# 38_DRAM-LPDDR4X_200P_1X32bit.net
KiCad netlist of a schematic drawn in Altium Designer
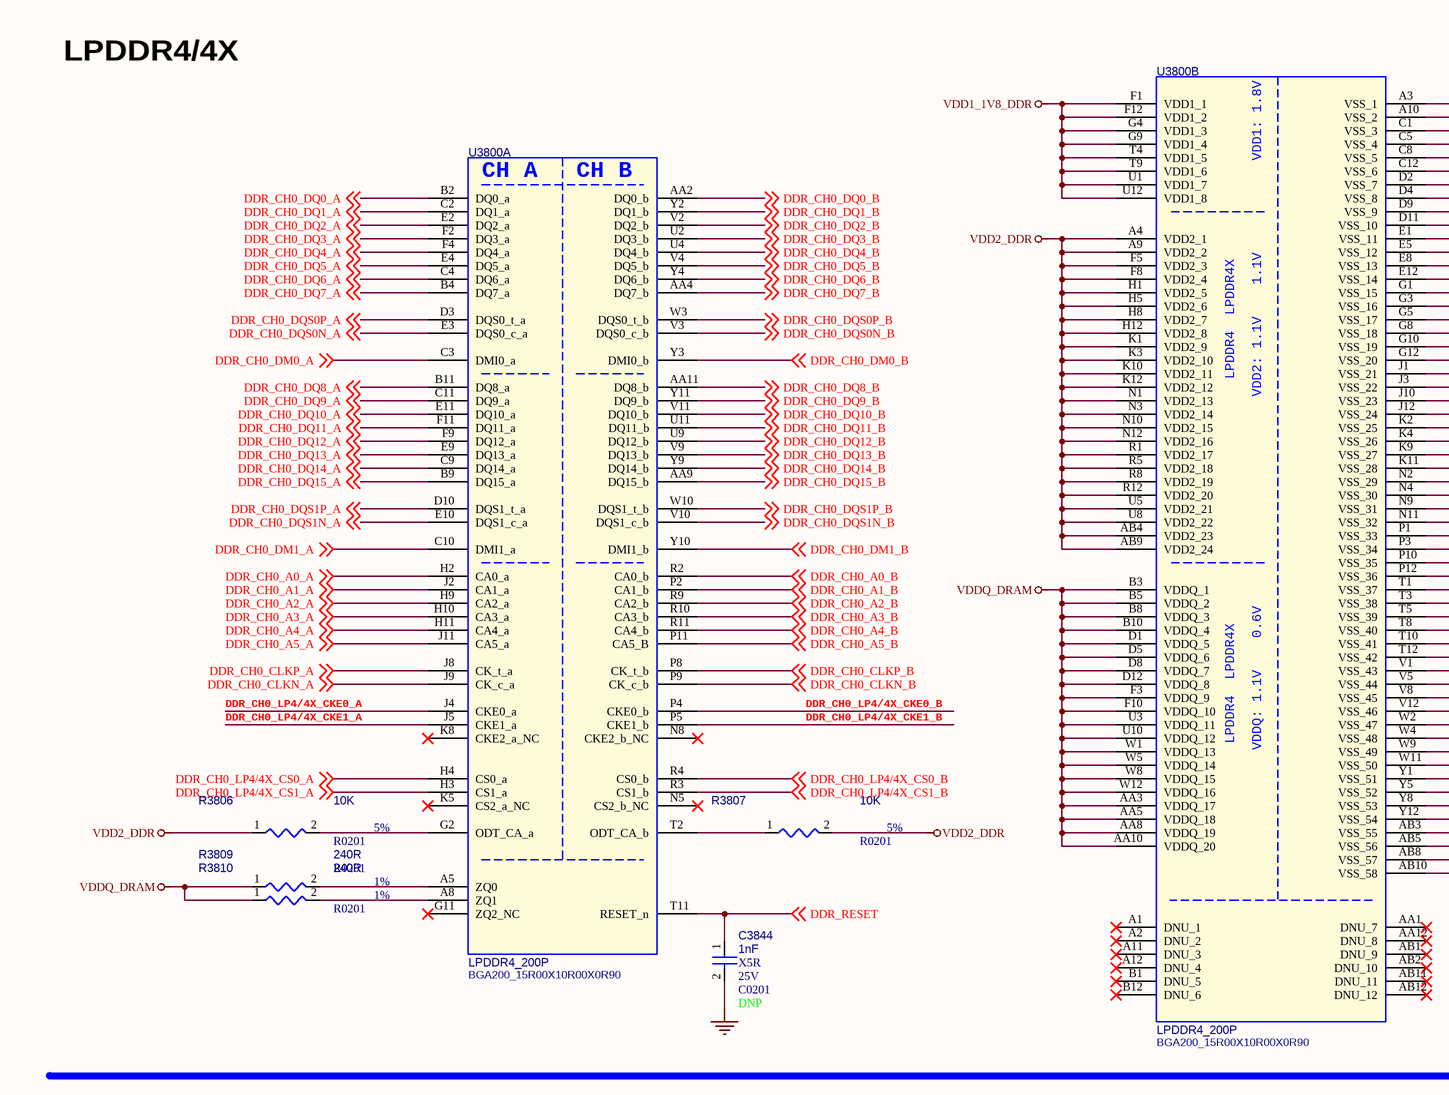
[diagram p0: 38.DRAM-LPDDR4X_200P_1X32bit.SchDoc, top left]
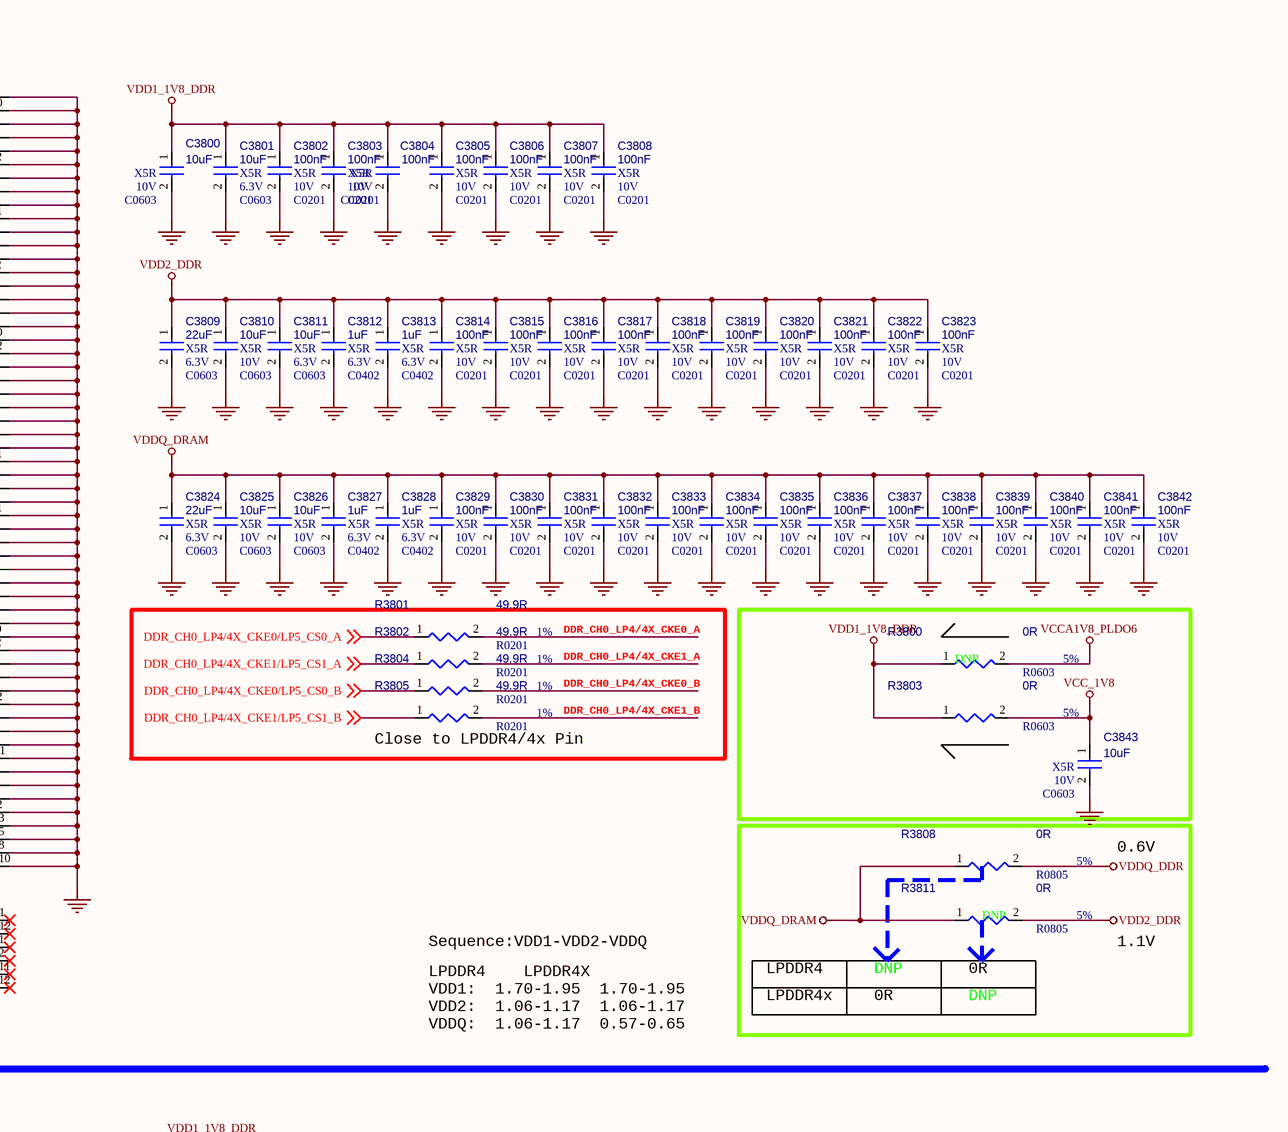
[diagram p1: 38.DRAM-LPDDR4X_200P_1X32bit.SchDoc, top right]
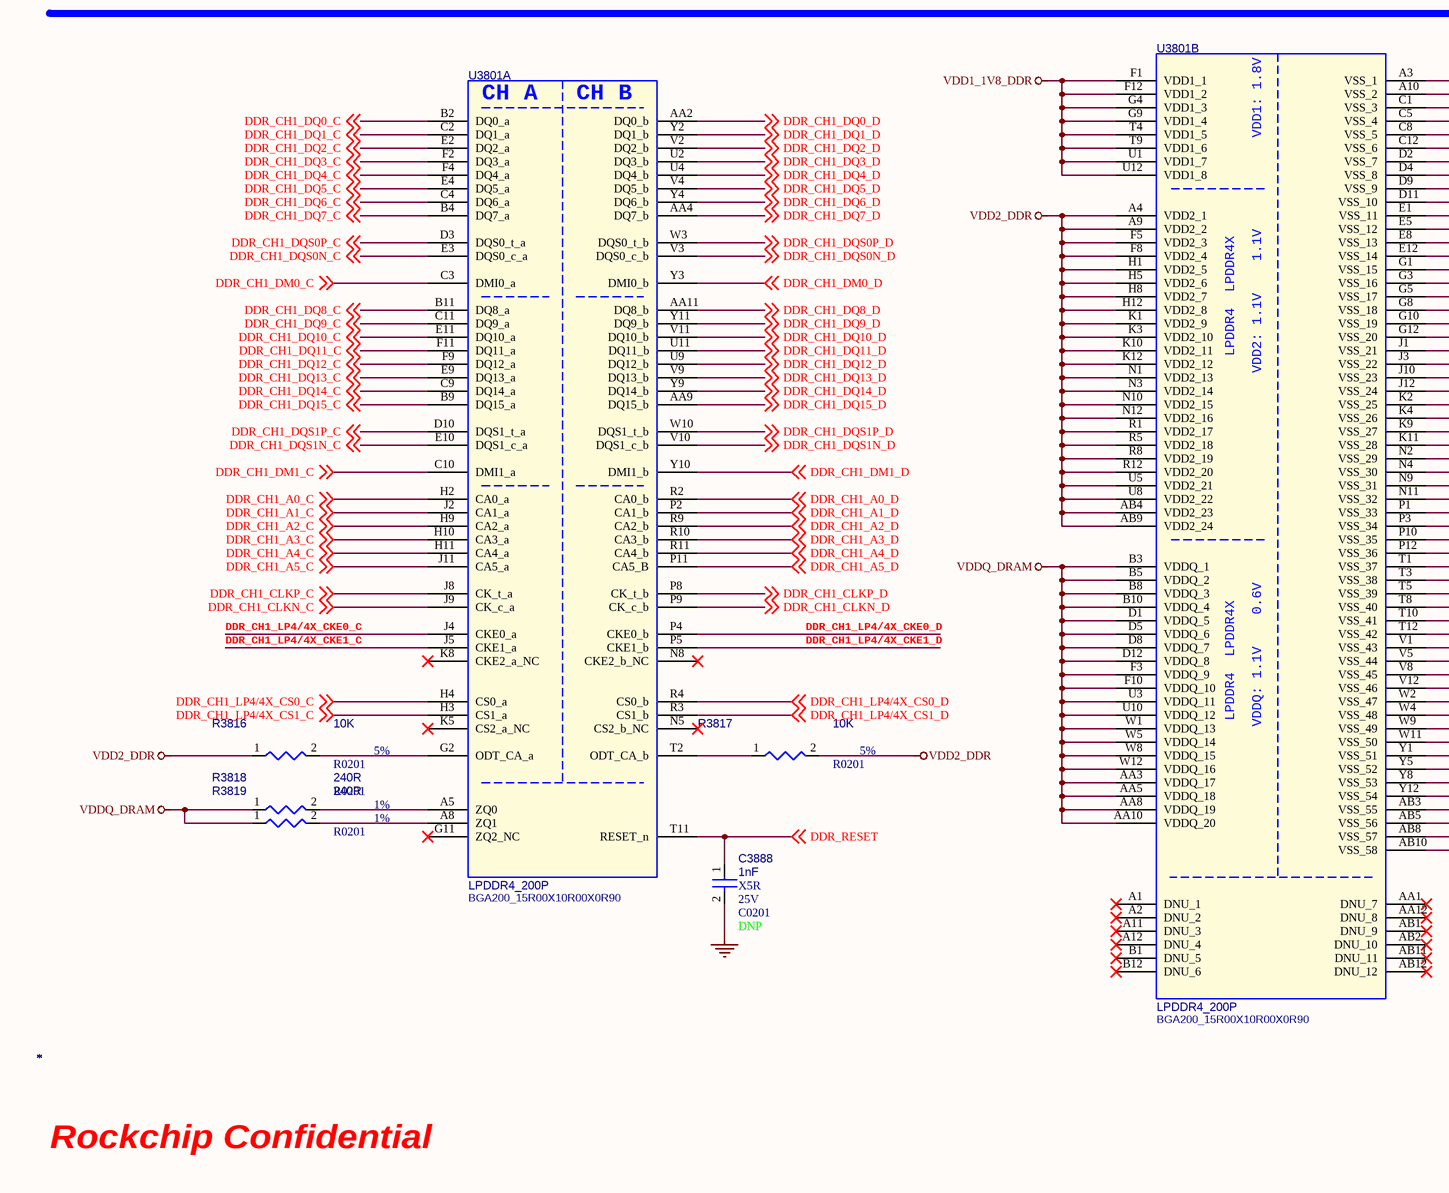
[diagram p2: 38.DRAM-LPDDR4X_200P_1X32bit.SchDoc, bottom left]
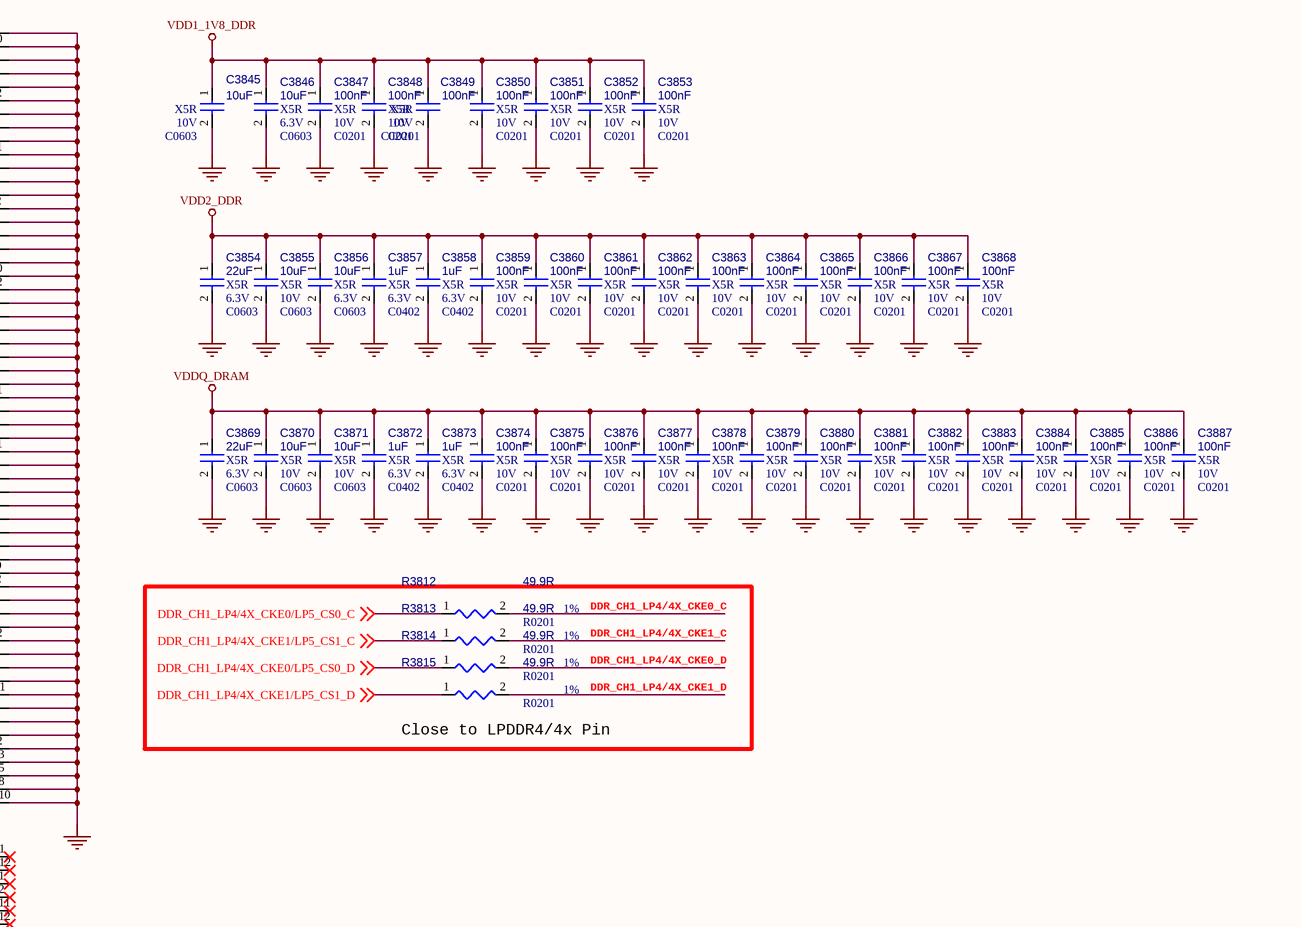
[diagram p3: 38.DRAM-LPDDR4X_200P_1X32bit.SchDoc, bottom right]

(export (version "E")
  (design (tool "Eeschema 10.0.6"))
  (components
    (comp (ref "C3800")
      (value "*")
      (footprint "C0603")
      (description "cap,10.00uF,+/-10%,10V,X5R,C0603")
      (fields
        (field (name "VOLTAGE") "10V")
        (field (name "PCB FOOTPRINT") "C0603")
        (field (name "DIELECTRIC") "X5R")
        (field (name "TOLERANCE") "10%")
        (field (name "MANUFACTURER") "TDK")
        (field (name "ALTIUM_UNNAMED_1") "10uF")
        (field (name "CREATED BY") "JJJ")
      )
      (libsource (lib "*") (part "CAP NP"))
    )
    (comp (ref "C3801")
      (value "*")
      (footprint "C0603")
      (description "cap,10.00uF,+/-10%,6.3V,X5R,C0603")
      (fields
        (field (name "VOLTAGE") "6.3V")
        (field (name "PCB FOOTPRINT") "C0603")
        (field (name "DIELECTRIC") "X5R")
        (field (name "TOLERANCE") "10%")
        (field (name "MANUFACTURER") "TDK")
        (field (name "ALTIUM_UNNAMED_1") "10uF")
        (field (name "CREATED BY") "JJJ")
      )
      (libsource (lib "*") (part "CAP NP"))
    )
    (comp (ref "C3802")
      (value "*")
      (footprint "C0201")
      (description "cap,100.00nF,+/-10%,10V,X5R,C0201")
      (fields
        (field (name "VOLTAGE") "10V")
        (field (name "PCB FOOTPRINT") "C0201")
        (field (name "DIELECTRIC") "X5R")
        (field (name "MANUFACTURER") "TDK")
        (field (name "TOLERANCE") "10%")
        (field (name "ALTIUM_UNNAMED_1") "100nF")
        (field (name "CREATED BY") "JJJ")
      )
      (libsource (lib "*") (part "CAP NP"))
    )
    (comp (ref "C3803")
      (value "*")
      (footprint "C0201")
      (description "cap,100.00nF,+/-10%,10V,X5R,C0201")
      (fields
        (field (name "VOLTAGE") "10V")
        (field (name "PCB FOOTPRINT") "C0201")
        (field (name "DIELECTRIC") "X5R")
        (field (name "TOLERANCE") "10%")
        (field (name "MANUFACTURER") "TDK")
        (field (name "ALTIUM_UNNAMED_1") "100nF")
        (field (name "CREATED BY") "JJJ")
      )
      (libsource (lib "*") (part "CAP NP"))
    )
    (comp (ref "C3804")
      (value "*")
      (footprint "C0201")
      (description "cap,100.00nF,+/-10%,10V,X5R,C0201")
      (fields
        (field (name "VOLTAGE") "10V")
        (field (name "PCB FOOTPRINT") "C0201")
        (field (name "DIELECTRIC") "X5R")
        (field (name "MANUFACTURER") "TDK")
        (field (name "TOLERANCE") "10%")
        (field (name "ALTIUM_UNNAMED_1") "100nF")
        (field (name "CREATED BY") "JJJ")
      )
      (libsource (lib "*") (part "CAP NP"))
    )
    (comp (ref "C3805")
      (value "*")
      (footprint "C0201")
      (description "cap,100.00nF,+/-10%,10V,X5R,C0201")
      (fields
        (field (name "VOLTAGE") "10V")
        (field (name "PCB FOOTPRINT") "C0201")
        (field (name "DIELECTRIC") "X5R")
        (field (name "MANUFACTURER") "TDK")
        (field (name "TOLERANCE") "10%")
        (field (name "ALTIUM_UNNAMED_1") "100nF")
        (field (name "CREATED BY") "JJJ")
      )
      (libsource (lib "*") (part "CAP NP"))
    )
    (comp (ref "C3806")
      (value "*")
      (footprint "C0201")
      (description "cap,100.00nF,+/-10%,10V,X5R,C0201")
      (fields
        (field (name "VOLTAGE") "10V")
        (field (name "PCB FOOTPRINT") "C0201")
        (field (name "DIELECTRIC") "X5R")
        (field (name "MANUFACTURER") "TDK")
        (field (name "TOLERANCE") "10%")
        (field (name "ALTIUM_UNNAMED_1") "100nF")
        (field (name "CREATED BY") "JJJ")
      )
      (libsource (lib "*") (part "CAP NP"))
    )
    (comp (ref "C3807")
      (value "*")
      (footprint "C0201")
      (description "cap,100.00nF,+/-10%,10V,X5R,C0201")
      (fields
        (field (name "VOLTAGE") "10V")
        (field (name "PCB FOOTPRINT") "C0201")
        (field (name "DIELECTRIC") "X5R")
        (field (name "TOLERANCE") "10%")
        (field (name "MANUFACTURER") "TDK")
        (field (name "ALTIUM_UNNAMED_1") "100nF")
        (field (name "CREATED BY") "JJJ")
      )
      (libsource (lib "*") (part "CAP NP"))
    )
    (comp (ref "C3808")
      (value "*")
      (footprint "C0201")
      (description "cap,100.00nF,+/-10%,10V,X5R,C0201")
      (fields
        (field (name "VOLTAGE") "10V")
        (field (name "PCB FOOTPRINT") "C0201")
        (field (name "DIELECTRIC") "X5R")
        (field (name "TOLERANCE") "10%")
        (field (name "MANUFACTURER") "TDK")
        (field (name "ALTIUM_UNNAMED_1") "100nF")
        (field (name "CREATED BY") "JJJ")
      )
      (libsource (lib "*") (part "CAP NP"))
    )
    (comp (ref "C3809")
      (value "*")
      (footprint "C0603")
      (description "cap,22.00uF,+/-20%,6.3V,X5R,C0603")
      (fields
        (field (name "VOLTAGE") "6.3V")
        (field (name "PCB FOOTPRINT") "C0603")
        (field (name "DIELECTRIC") "X5R")
        (field (name "TOLERANCE") "20%")
        (field (name "MANUFACTURER") "TDK")
        (field (name "ALTIUM_UNNAMED_1") "22uF")
        (field (name "CREATED BY") "JJJ")
      )
      (libsource (lib "*") (part "CAP NP"))
    )
    (comp (ref "C3810")
      (value "*")
      (footprint "C0603")
      (description "cap,10.00uF,+/-10%,10V,X5R,C0603")
      (fields
        (field (name "VOLTAGE") "10V")
        (field (name "PCB FOOTPRINT") "C0603")
        (field (name "DIELECTRIC") "X5R")
        (field (name "TOLERANCE") "10%")
        (field (name "MANUFACTURER") "TDK")
        (field (name "ALTIUM_UNNAMED_1") "10uF")
        (field (name "CREATED BY") "JJJ")
      )
      (libsource (lib "*") (part "CAP NP"))
    )
    (comp (ref "C3811")
      (value "*")
      (footprint "C0603")
      (description "cap,10.00uF,+/-10%,6.3V,X5R,C0603")
      (fields
        (field (name "VOLTAGE") "6.3V")
        (field (name "PCB FOOTPRINT") "C0603")
        (field (name "DIELECTRIC") "X5R")
        (field (name "TOLERANCE") "10%")
        (field (name "MANUFACTURER") "TDK")
        (field (name "ALTIUM_UNNAMED_1") "10uF")
        (field (name "CREATED BY") "JJJ")
      )
      (libsource (lib "*") (part "CAP NP"))
    )
    (comp (ref "C3812")
      (value "*")
      (footprint "C0402")
      (description "cap,1.00uF,+/-10%,6.3V,X5R,C0402")
      (fields
        (field (name "VOLTAGE") "6.3V")
        (field (name "PCB FOOTPRINT") "C0402")
        (field (name "DIELECTRIC") "X5R")
        (field (name "TOLERANCE") "10%")
        (field (name "MANUFACTURER") "TDK")
        (field (name "ALTIUM_UNNAMED_1") "1uF")
        (field (name "CREATED BY") "JJJ")
      )
      (libsource (lib "*") (part "CAP NP"))
    )
    (comp (ref "C3813")
      (value "*")
      (footprint "C0402")
      (description "cap,1.00uF,+/-10%,6.3V,X5R,C0402")
      (fields
        (field (name "VOLTAGE") "6.3V")
        (field (name "PCB FOOTPRINT") "C0402")
        (field (name "DIELECTRIC") "X5R")
        (field (name "TOLERANCE") "10%")
        (field (name "MANUFACTURER") "TDK")
        (field (name "ALTIUM_UNNAMED_1") "1uF")
        (field (name "CREATED BY") "JJJ")
      )
      (libsource (lib "*") (part "CAP NP"))
    )
    (comp (ref "C3814")
      (value "*")
      (footprint "C0201")
      (description "cap,100.00nF,+/-10%,10V,X5R,C0201")
      (fields
        (field (name "VOLTAGE") "10V")
        (field (name "PCB FOOTPRINT") "C0201")
        (field (name "DIELECTRIC") "X5R")
        (field (name "TOLERANCE") "10%")
        (field (name "MANUFACTURER") "TDK")
        (field (name "ALTIUM_UNNAMED_1") "100nF")
        (field (name "CREATED BY") "JJJ")
      )
      (libsource (lib "*") (part "CAP NP"))
    )
    (comp (ref "C3815")
      (value "*")
      (footprint "C0201")
      (description "cap,100.00nF,+/-10%,10V,X5R,C0201")
      (fields
        (field (name "VOLTAGE") "10V")
        (field (name "PCB FOOTPRINT") "C0201")
        (field (name "DIELECTRIC") "X5R")
        (field (name "TOLERANCE") "10%")
        (field (name "MANUFACTURER") "TDK")
        (field (name "ALTIUM_UNNAMED_1") "100nF")
        (field (name "CREATED BY") "JJJ")
      )
      (libsource (lib "*") (part "CAP NP"))
    )
    (comp (ref "C3816")
      (value "*")
      (footprint "C0201")
      (description "cap,100.00nF,+/-10%,10V,X5R,C0201")
      (fields
        (field (name "VOLTAGE") "10V")
        (field (name "PCB FOOTPRINT") "C0201")
        (field (name "DIELECTRIC") "X5R")
        (field (name "MANUFACTURER") "TDK")
        (field (name "TOLERANCE") "10%")
        (field (name "ALTIUM_UNNAMED_1") "100nF")
        (field (name "CREATED BY") "JJJ")
      )
      (libsource (lib "*") (part "CAP NP"))
    )
    (comp (ref "C3817")
      (value "*")
      (footprint "C0201")
      (description "cap,100.00nF,+/-10%,10V,X5R,C0201")
      (fields
        (field (name "VOLTAGE") "10V")
        (field (name "PCB FOOTPRINT") "C0201")
        (field (name "DIELECTRIC") "X5R")
        (field (name "TOLERANCE") "10%")
        (field (name "MANUFACTURER") "TDK")
        (field (name "ALTIUM_UNNAMED_1") "100nF")
        (field (name "CREATED BY") "JJJ")
      )
      (libsource (lib "*") (part "CAP NP"))
    )
    (comp (ref "C3818")
      (value "*")
      (footprint "C0201")
      (description "cap,100.00nF,+/-10%,10V,X5R,C0201")
      (fields
        (field (name "VOLTAGE") "10V")
        (field (name "PCB FOOTPRINT") "C0201")
        (field (name "DIELECTRIC") "X5R")
        (field (name "TOLERANCE") "10%")
        (field (name "MANUFACTURER") "TDK")
        (field (name "ALTIUM_UNNAMED_1") "100nF")
        (field (name "CREATED BY") "JJJ")
      )
      (libsource (lib "*") (part "CAP NP"))
    )
    (comp (ref "C3819")
      (value "*")
      (footprint "C0201")
      (description "cap,100.00nF,+/-10%,10V,X5R,C0201")
      (fields
        (field (name "VOLTAGE") "10V")
        (field (name "PCB FOOTPRINT") "C0201")
        (field (name "DIELECTRIC") "X5R")
        (field (name "MANUFACTURER") "TDK")
        (field (name "TOLERANCE") "10%")
        (field (name "ALTIUM_UNNAMED_1") "100nF")
        (field (name "CREATED BY") "JJJ")
      )
      (libsource (lib "*") (part "CAP NP"))
    )
    (comp (ref "C3820")
      (value "*")
      (footprint "C0201")
      (description "cap,100.00nF,+/-10%,10V,X5R,C0201")
      (fields
        (field (name "VOLTAGE") "10V")
        (field (name "PCB FOOTPRINT") "C0201")
        (field (name "DIELECTRIC") "X5R")
        (field (name "MANUFACTURER") "TDK")
        (field (name "TOLERANCE") "10%")
        (field (name "ALTIUM_UNNAMED_1") "100nF")
        (field (name "CREATED BY") "JJJ")
      )
      (libsource (lib "*") (part "CAP NP"))
    )
    (comp (ref "C3821")
      (value "*")
      (footprint "C0201")
      (description "cap,100.00nF,+/-10%,10V,X5R,C0201")
      (fields
        (field (name "VOLTAGE") "10V")
        (field (name "PCB FOOTPRINT") "C0201")
        (field (name "DIELECTRIC") "X5R")
        (field (name "TOLERANCE") "10%")
        (field (name "MANUFACTURER") "TDK")
        (field (name "ALTIUM_UNNAMED_1") "100nF")
        (field (name "CREATED BY") "JJJ")
      )
      (libsource (lib "*") (part "CAP NP"))
    )
    (comp (ref "C3822")
      (value "*")
      (footprint "C0201")
      (description "cap,100.00nF,+/-10%,10V,X5R,C0201")
      (fields
        (field (name "VOLTAGE") "10V")
        (field (name "PCB FOOTPRINT") "C0201")
        (field (name "DIELECTRIC") "X5R")
        (field (name "MANUFACTURER") "TDK")
        (field (name "TOLERANCE") "10%")
        (field (name "ALTIUM_UNNAMED_1") "100nF")
        (field (name "CREATED BY") "JJJ")
      )
      (libsource (lib "*") (part "CAP NP"))
    )
    (comp (ref "C3823")
      (value "*")
      (footprint "C0201")
      (description "cap,100.00nF,+/-10%,10V,X5R,C0201")
      (fields
        (field (name "VOLTAGE") "10V")
        (field (name "PCB FOOTPRINT") "C0201")
        (field (name "DIELECTRIC") "X5R")
        (field (name "TOLERANCE") "10%")
        (field (name "MANUFACTURER") "TDK")
        (field (name "ALTIUM_UNNAMED_1") "100nF")
        (field (name "CREATED BY") "JJJ")
      )
      (libsource (lib "*") (part "CAP NP"))
    )
    (comp (ref "C3824")
      (value "*")
      (footprint "C0603")
      (description "cap,22.00uF,+/-20%,6.3V,X5R,C0603")
      (fields
        (field (name "VOLTAGE") "6.3V")
        (field (name "PCB FOOTPRINT") "C0603")
        (field (name "DIELECTRIC") "X5R")
        (field (name "MANUFACTURER") "TDK")
        (field (name "TOLERANCE") "20%")
        (field (name "ALTIUM_UNNAMED_1") "22uF")
        (field (name "CREATED BY") "JJJ")
      )
      (libsource (lib "*") (part "CAP NP"))
    )
    (comp (ref "C3825")
      (value "*")
      (footprint "C0603")
      (description "cap,10.00uF,+/-10%,10V,X5R,C0603")
      (fields
        (field (name "VOLTAGE") "10V")
        (field (name "PCB FOOTPRINT") "C0603")
        (field (name "DIELECTRIC") "X5R")
        (field (name "TOLERANCE") "10%")
        (field (name "MANUFACTURER") "TDK")
        (field (name "ALTIUM_UNNAMED_1") "10uF")
        (field (name "CREATED BY") "JJJ")
      )
      (libsource (lib "*") (part "CAP NP"))
    )
    (comp (ref "C3826")
      (value "*")
      (footprint "C0603")
      (description "cap,10.00uF,+/-10%,10V,X5R,C0603")
      (fields
        (field (name "VOLTAGE") "10V")
        (field (name "PCB FOOTPRINT") "C0603")
        (field (name "DIELECTRIC") "X5R")
        (field (name "MANUFACTURER") "TDK")
        (field (name "TOLERANCE") "10%")
        (field (name "ALTIUM_UNNAMED_1") "10uF")
        (field (name "CREATED BY") "JJJ")
      )
      (libsource (lib "*") (part "CAP NP"))
    )
    (comp (ref "C3827")
      (value "*")
      (footprint "C0402")
      (description "cap,1.00uF,+/-10%,6.3V,X5R,C0402")
      (fields
        (field (name "VOLTAGE") "6.3V")
        (field (name "PCB FOOTPRINT") "C0402")
        (field (name "DIELECTRIC") "X5R")
        (field (name "MANUFACTURER") "TDK")
        (field (name "TOLERANCE") "10%")
        (field (name "ALTIUM_UNNAMED_1") "1uF")
        (field (name "CREATED BY") "JJJ")
      )
      (libsource (lib "*") (part "CAP NP"))
    )
    (comp (ref "C3828")
      (value "*")
      (footprint "C0402")
      (description "cap,1.00uF,+/-10%,6.3V,X5R,C0402")
      (fields
        (field (name "VOLTAGE") "6.3V")
        (field (name "PCB FOOTPRINT") "C0402")
        (field (name "DIELECTRIC") "X5R")
        (field (name "MANUFACTURER") "TDK")
        (field (name "TOLERANCE") "10%")
        (field (name "ALTIUM_UNNAMED_1") "1uF")
        (field (name "CREATED BY") "JJJ")
      )
      (libsource (lib "*") (part "CAP NP"))
    )
    (comp (ref "C3829")
      (value "*")
      (footprint "C0201")
      (description "cap,100.00nF,+/-10%,10V,X5R,C0201")
      (fields
        (field (name "VOLTAGE") "10V")
        (field (name "PCB FOOTPRINT") "C0201")
        (field (name "DIELECTRIC") "X5R")
        (field (name "MANUFACTURER") "TDK")
        (field (name "TOLERANCE") "10%")
        (field (name "ALTIUM_UNNAMED_1") "100nF")
        (field (name "CREATED BY") "JJJ")
      )
      (libsource (lib "*") (part "CAP NP"))
    )
    (comp (ref "C3830")
      (value "*")
      (footprint "C0201")
      (description "cap,100.00nF,+/-10%,10V,X5R,C0201")
      (fields
        (field (name "VOLTAGE") "10V")
        (field (name "PCB FOOTPRINT") "C0201")
        (field (name "DIELECTRIC") "X5R")
        (field (name "MANUFACTURER") "TDK")
        (field (name "TOLERANCE") "10%")
        (field (name "ALTIUM_UNNAMED_1") "100nF")
        (field (name "CREATED BY") "JJJ")
      )
      (libsource (lib "*") (part "CAP NP"))
    )
    (comp (ref "C3831")
      (value "*")
      (footprint "C0201")
      (description "cap,100.00nF,+/-10%,10V,X5R,C0201")
      (fields
        (field (name "VOLTAGE") "10V")
        (field (name "PCB FOOTPRINT") "C0201")
        (field (name "DIELECTRIC") "X5R")
        (field (name "MANUFACTURER") "TDK")
        (field (name "TOLERANCE") "10%")
        (field (name "ALTIUM_UNNAMED_1") "100nF")
        (field (name "CREATED BY") "JJJ")
      )
      (libsource (lib "*") (part "CAP NP"))
    )
    (comp (ref "C3832")
      (value "*")
      (footprint "C0201")
      (description "cap,100.00nF,+/-10%,10V,X5R,C0201")
      (fields
        (field (name "VOLTAGE") "10V")
        (field (name "PCB FOOTPRINT") "C0201")
        (field (name "DIELECTRIC") "X5R")
        (field (name "TOLERANCE") "10%")
        (field (name "MANUFACTURER") "TDK")
        (field (name "ALTIUM_UNNAMED_1") "100nF")
        (field (name "CREATED BY") "JJJ")
      )
      (libsource (lib "*") (part "CAP NP"))
    )
    (comp (ref "C3833")
      (value "*")
      (footprint "C0201")
      (description "cap,100.00nF,+/-10%,10V,X5R,C0201")
      (fields
        (field (name "VOLTAGE") "10V")
        (field (name "PCB FOOTPRINT") "C0201")
        (field (name "DIELECTRIC") "X5R")
        (field (name "TOLERANCE") "10%")
        (field (name "MANUFACTURER") "TDK")
        (field (name "ALTIUM_UNNAMED_1") "100nF")
        (field (name "CREATED BY") "JJJ")
      )
      (libsource (lib "*") (part "CAP NP"))
    )
    (comp (ref "C3834")
      (value "*")
      (footprint "C0201")
      (description "cap,100.00nF,+/-10%,10V,X5R,C0201")
      (fields
        (field (name "VOLTAGE") "10V")
        (field (name "PCB FOOTPRINT") "C0201")
        (field (name "DIELECTRIC") "X5R")
        (field (name "TOLERANCE") "10%")
        (field (name "MANUFACTURER") "TDK")
        (field (name "ALTIUM_UNNAMED_1") "100nF")
        (field (name "CREATED BY") "JJJ")
      )
      (libsource (lib "*") (part "CAP NP"))
    )
    (comp (ref "C3835")
      (value "*")
      (footprint "C0201")
      (description "cap,100.00nF,+/-10%,10V,X5R,C0201")
      (fields
        (field (name "VOLTAGE") "10V")
        (field (name "PCB FOOTPRINT") "C0201")
        (field (name "DIELECTRIC") "X5R")
        (field (name "MANUFACTURER") "TDK")
        (field (name "TOLERANCE") "10%")
        (field (name "ALTIUM_UNNAMED_1") "100nF")
        (field (name "CREATED BY") "JJJ")
      )
      (libsource (lib "*") (part "CAP NP"))
    )
    (comp (ref "C3836")
      (value "*")
      (footprint "C0201")
      (description "cap,100.00nF,+/-10%,10V,X5R,C0201")
      (fields
        (field (name "VOLTAGE") "10V")
        (field (name "PCB FOOTPRINT") "C0201")
        (field (name "DIELECTRIC") "X5R")
        (field (name "TOLERANCE") "10%")
        (field (name "MANUFACTURER") "TDK")
        (field (name "ALTIUM_UNNAMED_1") "100nF")
        (field (name "CREATED BY") "JJJ")
      )
      (libsource (lib "*") (part "CAP NP"))
    )
    (comp (ref "C3837")
      (value "*")
      (footprint "C0201")
      (description "cap,100.00nF,+/-10%,10V,X5R,C0201")
      (fields
        (field (name "VOLTAGE") "10V")
        (field (name "PCB FOOTPRINT") "C0201")
        (field (name "DIELECTRIC") "X5R")
        (field (name "TOLERANCE") "10%")
        (field (name "MANUFACTURER") "TDK")
        (field (name "ALTIUM_UNNAMED_1") "100nF")
        (field (name "CREATED BY") "JJJ")
      )
      (libsource (lib "*") (part "CAP NP"))
    )
    (comp (ref "C3838")
      (value "*")
      (footprint "C0201")
      (description "cap,100.00nF,+/-10%,10V,X5R,C0201")
      (fields
        (field (name "VOLTAGE") "10V")
        (field (name "PCB FOOTPRINT") "C0201")
        (field (name "DIELECTRIC") "X5R")
        (field (name "MANUFACTURER") "TDK")
        (field (name "TOLERANCE") "10%")
        (field (name "ALTIUM_UNNAMED_1") "100nF")
        (field (name "CREATED BY") "JJJ")
      )
      (libsource (lib "*") (part "CAP NP"))
    )
    (comp (ref "C3839")
      (value "*")
      (footprint "C0201")
      (description "cap,100.00nF,+/-10%,10V,X5R,C0201")
      (fields
        (field (name "VOLTAGE") "10V")
        (field (name "PCB FOOTPRINT") "C0201")
        (field (name "DIELECTRIC") "X5R")
        (field (name "TOLERANCE") "10%")
        (field (name "MANUFACTURER") "TDK")
        (field (name "ALTIUM_UNNAMED_1") "100nF")
        (field (name "CREATED BY") "JJJ")
      )
      (libsource (lib "*") (part "CAP NP"))
    )
    (comp (ref "C3840")
      (value "*")
      (footprint "C0201")
      (description "cap,100.00nF,+/-10%,10V,X5R,C0201")
      (fields
        (field (name "VOLTAGE") "10V")
        (field (name "PCB FOOTPRINT") "C0201")
        (field (name "DIELECTRIC") "X5R")
        (field (name "MANUFACTURER") "TDK")
        (field (name "TOLERANCE") "10%")
        (field (name "ALTIUM_UNNAMED_1") "100nF")
        (field (name "CREATED BY") "JJJ")
      )
      (libsource (lib "*") (part "CAP NP"))
    )
    (comp (ref "C3841")
      (value "*")
      (footprint "C0201")
      (description "cap,100.00nF,+/-10%,10V,X5R,C0201")
      (fields
        (field (name "VOLTAGE") "10V")
        (field (name "PCB FOOTPRINT") "C0201")
        (field (name "DIELECTRIC") "X5R")
        (field (name "MANUFACTURER") "TDK")
        (field (name "TOLERANCE") "10%")
        (field (name "ALTIUM_UNNAMED_1") "100nF")
        (field (name "CREATED BY") "JJJ")
      )
      (libsource (lib "*") (part "CAP NP"))
    )
    (comp (ref "C3842")
      (value "*")
      (footprint "C0201")
      (description "cap,100.00nF,+/-10%,10V,X5R,C0201")
      (fields
        (field (name "VOLTAGE") "10V")
        (field (name "PCB FOOTPRINT") "C0201")
        (field (name "DIELECTRIC") "X5R")
        (field (name "MANUFACTURER") "TDK")
        (field (name "TOLERANCE") "10%")
        (field (name "ALTIUM_UNNAMED_1") "100nF")
        (field (name "CREATED BY") "JJJ")
      )
      (libsource (lib "*") (part "CAP NP"))
    )
    (comp (ref "C3843")
      (value "*")
      (footprint "C0603")
      (description "cap,10.00uF,+/-10%,10V,X5R,C0603")
      (fields
        (field (name "VOLTAGE") "10V")
        (field (name "PCB FOOTPRINT") "C0603")
        (field (name "DIELECTRIC") "X5R")
        (field (name "MANUFACTURER") "TDK")
        (field (name "TOLERANCE") "10%")
        (field (name "ALTIUM_UNNAMED_1") "10uF")
        (field (name "CREATED BY") "JJJ")
      )
      (libsource (lib "*") (part "CAP NP"))
    )
    (comp (ref "C3844")
      (value "*")
      (footprint "C0201")
      (description "cap,1.00nF,+/-10%,25V,X5R,C0201")
      (fields
        (field (name "VOLTAGE") "25V")
        (field (name "PCB FOOTPRINT") "C0201")
        (field (name "DIELECTRIC") "X5R")
        (field (name "MANUFACTURER") "TDK")
        (field (name "TOLERANCE") "10%")
        (field (name "OPTION") "DNP")
        (field (name "ALTIUM_UNNAMED_1") "1nF")
        (field (name "CREATED BY") "JJJ")
      )
      (libsource (lib "*") (part "CAP NP"))
    )
    (comp (ref "C3845")
      (value "*")
      (footprint "C0603")
      (description "cap,10.00uF,+/-10%,10V,X5R,C0603")
      (fields
        (field (name "VOLTAGE") "10V")
        (field (name "PCB FOOTPRINT") "C0603")
        (field (name "DIELECTRIC") "X5R")
        (field (name "TOLERANCE") "10%")
        (field (name "MANUFACTURER") "TDK")
        (field (name "ALTIUM_UNNAMED_1") "10uF")
        (field (name "CREATED BY") "JJJ")
      )
      (libsource (lib "*") (part "CAP NP"))
    )
    (comp (ref "C3846")
      (value "*")
      (footprint "C0603")
      (description "cap,10.00uF,+/-10%,6.3V,X5R,C0603")
      (fields
        (field (name "VOLTAGE") "6.3V")
        (field (name "PCB FOOTPRINT") "C0603")
        (field (name "DIELECTRIC") "X5R")
        (field (name "TOLERANCE") "10%")
        (field (name "MANUFACTURER") "TDK")
        (field (name "ALTIUM_UNNAMED_1") "10uF")
        (field (name "CREATED BY") "JJJ")
      )
      (libsource (lib "*") (part "CAP NP"))
    )
    (comp (ref "C3847")
      (value "*")
      (footprint "C0201")
      (description "cap,100.00nF,+/-10%,10V,X5R,C0201")
      (fields
        (field (name "VOLTAGE") "10V")
        (field (name "PCB FOOTPRINT") "C0201")
        (field (name "DIELECTRIC") "X5R")
        (field (name "MANUFACTURER") "TDK")
        (field (name "TOLERANCE") "10%")
        (field (name "ALTIUM_UNNAMED_1") "100nF")
        (field (name "CREATED BY") "JJJ")
      )
      (libsource (lib "*") (part "CAP NP"))
    )
    (comp (ref "C3848")
      (value "*")
      (footprint "C0201")
      (description "cap,100.00nF,+/-10%,10V,X5R,C0201")
      (fields
        (field (name "VOLTAGE") "10V")
        (field (name "PCB FOOTPRINT") "C0201")
        (field (name "DIELECTRIC") "X5R")
        (field (name "TOLERANCE") "10%")
        (field (name "MANUFACTURER") "TDK")
        (field (name "ALTIUM_UNNAMED_1") "100nF")
        (field (name "CREATED BY") "JJJ")
      )
      (libsource (lib "*") (part "CAP NP"))
    )
    (comp (ref "C3849")
      (value "*")
      (footprint "C0201")
      (description "cap,100.00nF,+/-10%,10V,X5R,C0201")
      (fields
        (field (name "VOLTAGE") "10V")
        (field (name "PCB FOOTPRINT") "C0201")
        (field (name "DIELECTRIC") "X5R")
        (field (name "MANUFACTURER") "TDK")
        (field (name "TOLERANCE") "10%")
        (field (name "ALTIUM_UNNAMED_1") "100nF")
        (field (name "CREATED BY") "JJJ")
      )
      (libsource (lib "*") (part "CAP NP"))
    )
    (comp (ref "C3850")
      (value "*")
      (footprint "C0201")
      (description "cap,100.00nF,+/-10%,10V,X5R,C0201")
      (fields
        (field (name "VOLTAGE") "10V")
        (field (name "PCB FOOTPRINT") "C0201")
        (field (name "DIELECTRIC") "X5R")
        (field (name "MANUFACTURER") "TDK")
        (field (name "TOLERANCE") "10%")
        (field (name "ALTIUM_UNNAMED_1") "100nF")
        (field (name "CREATED BY") "JJJ")
      )
      (libsource (lib "*") (part "CAP NP"))
    )
    (comp (ref "C3851")
      (value "*")
      (footprint "C0201")
      (description "cap,100.00nF,+/-10%,10V,X5R,C0201")
      (fields
        (field (name "VOLTAGE") "10V")
        (field (name "PCB FOOTPRINT") "C0201")
        (field (name "DIELECTRIC") "X5R")
        (field (name "MANUFACTURER") "TDK")
        (field (name "TOLERANCE") "10%")
        (field (name "ALTIUM_UNNAMED_1") "100nF")
        (field (name "CREATED BY") "JJJ")
      )
      (libsource (lib "*") (part "CAP NP"))
    )
    (comp (ref "C3852")
      (value "*")
      (footprint "C0201")
      (description "cap,100.00nF,+/-10%,10V,X5R,C0201")
      (fields
        (field (name "VOLTAGE") "10V")
        (field (name "PCB FOOTPRINT") "C0201")
        (field (name "DIELECTRIC") "X5R")
        (field (name "TOLERANCE") "10%")
        (field (name "MANUFACTURER") "TDK")
        (field (name "ALTIUM_UNNAMED_1") "100nF")
        (field (name "CREATED BY") "JJJ")
      )
      (libsource (lib "*") (part "CAP NP"))
    )
    (comp (ref "C3853")
      (value "*")
      (footprint "C0201")
      (description "cap,100.00nF,+/-10%,10V,X5R,C0201")
      (fields
        (field (name "VOLTAGE") "10V")
        (field (name "PCB FOOTPRINT") "C0201")
        (field (name "DIELECTRIC") "X5R")
        (field (name "TOLERANCE") "10%")
        (field (name "MANUFACTURER") "TDK")
        (field (name "ALTIUM_UNNAMED_1") "100nF")
        (field (name "CREATED BY") "JJJ")
      )
      (libsource (lib "*") (part "CAP NP"))
    )
    (comp (ref "C3854")
      (value "*")
      (footprint "C0603")
      (description "cap,22.00uF,+/-20%,6.3V,X5R,C0603")
      (fields
        (field (name "VOLTAGE") "6.3V")
        (field (name "PCB FOOTPRINT") "C0603")
        (field (name "DIELECTRIC") "X5R")
        (field (name "TOLERANCE") "20%")
        (field (name "MANUFACTURER") "TDK")
        (field (name "ALTIUM_UNNAMED_1") "22uF")
        (field (name "CREATED BY") "JJJ")
      )
      (libsource (lib "*") (part "CAP NP"))
    )
    (comp (ref "C3855")
      (value "*")
      (footprint "C0603")
      (description "cap,10.00uF,+/-10%,10V,X5R,C0603")
      (fields
        (field (name "VOLTAGE") "10V")
        (field (name "PCB FOOTPRINT") "C0603")
        (field (name "DIELECTRIC") "X5R")
        (field (name "TOLERANCE") "10%")
        (field (name "MANUFACTURER") "TDK")
        (field (name "ALTIUM_UNNAMED_1") "10uF")
        (field (name "CREATED BY") "JJJ")
      )
      (libsource (lib "*") (part "CAP NP"))
    )
    (comp (ref "C3856")
      (value "*")
      (footprint "C0603")
      (description "cap,10.00uF,+/-10%,6.3V,X5R,C0603")
      (fields
        (field (name "VOLTAGE") "6.3V")
        (field (name "PCB FOOTPRINT") "C0603")
        (field (name "DIELECTRIC") "X5R")
        (field (name "TOLERANCE") "10%")
        (field (name "MANUFACTURER") "TDK")
        (field (name "ALTIUM_UNNAMED_1") "10uF")
        (field (name "CREATED BY") "JJJ")
      )
      (libsource (lib "*") (part "CAP NP"))
    )
    (comp (ref "C3857")
      (value "*")
      (footprint "C0402")
      (description "cap,1.00uF,+/-10%,6.3V,X5R,C0402")
      (fields
        (field (name "VOLTAGE") "6.3V")
        (field (name "PCB FOOTPRINT") "C0402")
        (field (name "DIELECTRIC") "X5R")
        (field (name "TOLERANCE") "10%")
        (field (name "MANUFACTURER") "TDK")
        (field (name "ALTIUM_UNNAMED_1") "1uF")
        (field (name "CREATED BY") "JJJ")
      )
      (libsource (lib "*") (part "CAP NP"))
    )
    (comp (ref "C3858")
      (value "*")
      (footprint "C0402")
      (description "cap,1.00uF,+/-10%,6.3V,X5R,C0402")
      (fields
        (field (name "VOLTAGE") "6.3V")
        (field (name "PCB FOOTPRINT") "C0402")
        (field (name "DIELECTRIC") "X5R")
        (field (name "TOLERANCE") "10%")
        (field (name "MANUFACTURER") "TDK")
        (field (name "ALTIUM_UNNAMED_1") "1uF")
        (field (name "CREATED BY") "JJJ")
      )
      (libsource (lib "*") (part "CAP NP"))
    )
    (comp (ref "C3859")
      (value "*")
      (footprint "C0201")
      (description "cap,100.00nF,+/-10%,10V,X5R,C0201")
      (fields
        (field (name "VOLTAGE") "10V")
        (field (name "PCB FOOTPRINT") "C0201")
        (field (name "DIELECTRIC") "X5R")
        (field (name "TOLERANCE") "10%")
        (field (name "MANUFACTURER") "TDK")
        (field (name "ALTIUM_UNNAMED_1") "100nF")
        (field (name "CREATED BY") "JJJ")
      )
      (libsource (lib "*") (part "CAP NP"))
    )
    (comp (ref "C3860")
      (value "*")
      (footprint "C0201")
      (description "cap,100.00nF,+/-10%,10V,X5R,C0201")
      (fields
        (field (name "VOLTAGE") "10V")
        (field (name "PCB FOOTPRINT") "C0201")
        (field (name "DIELECTRIC") "X5R")
        (field (name "TOLERANCE") "10%")
        (field (name "MANUFACTURER") "TDK")
        (field (name "ALTIUM_UNNAMED_1") "100nF")
        (field (name "CREATED BY") "JJJ")
      )
      (libsource (lib "*") (part "CAP NP"))
    )
    (comp (ref "C3861")
      (value "*")
      (footprint "C0201")
      (description "cap,100.00nF,+/-10%,10V,X5R,C0201")
      (fields
        (field (name "VOLTAGE") "10V")
        (field (name "PCB FOOTPRINT") "C0201")
        (field (name "DIELECTRIC") "X5R")
        (field (name "MANUFACTURER") "TDK")
        (field (name "TOLERANCE") "10%")
        (field (name "ALTIUM_UNNAMED_1") "100nF")
        (field (name "CREATED BY") "JJJ")
      )
      (libsource (lib "*") (part "CAP NP"))
    )
    (comp (ref "C3862")
      (value "*")
      (footprint "C0201")
      (description "cap,100.00nF,+/-10%,10V,X5R,C0201")
      (fields
        (field (name "VOLTAGE") "10V")
        (field (name "PCB FOOTPRINT") "C0201")
        (field (name "DIELECTRIC") "X5R")
        (field (name "TOLERANCE") "10%")
        (field (name "MANUFACTURER") "TDK")
        (field (name "ALTIUM_UNNAMED_1") "100nF")
        (field (name "CREATED BY") "JJJ")
      )
      (libsource (lib "*") (part "CAP NP"))
    )
    (comp (ref "C3863")
      (value "*")
      (footprint "C0201")
      (description "cap,100.00nF,+/-10%,10V,X5R,C0201")
      (fields
        (field (name "VOLTAGE") "10V")
        (field (name "PCB FOOTPRINT") "C0201")
        (field (name "DIELECTRIC") "X5R")
        (field (name "TOLERANCE") "10%")
        (field (name "MANUFACTURER") "TDK")
        (field (name "ALTIUM_UNNAMED_1") "100nF")
        (field (name "CREATED BY") "JJJ")
      )
      (libsource (lib "*") (part "CAP NP"))
    )
    (comp (ref "C3864")
      (value "*")
      (footprint "C0201")
      (description "cap,100.00nF,+/-10%,10V,X5R,C0201")
      (fields
        (field (name "VOLTAGE") "10V")
        (field (name "PCB FOOTPRINT") "C0201")
        (field (name "DIELECTRIC") "X5R")
        (field (name "MANUFACTURER") "TDK")
        (field (name "TOLERANCE") "10%")
        (field (name "ALTIUM_UNNAMED_1") "100nF")
        (field (name "CREATED BY") "JJJ")
      )
      (libsource (lib "*") (part "CAP NP"))
    )
    (comp (ref "C3865")
      (value "*")
      (footprint "C0201")
      (description "cap,100.00nF,+/-10%,10V,X5R,C0201")
      (fields
        (field (name "VOLTAGE") "10V")
        (field (name "PCB FOOTPRINT") "C0201")
        (field (name "DIELECTRIC") "X5R")
        (field (name "MANUFACTURER") "TDK")
        (field (name "TOLERANCE") "10%")
        (field (name "ALTIUM_UNNAMED_1") "100nF")
        (field (name "CREATED BY") "JJJ")
      )
      (libsource (lib "*") (part "CAP NP"))
    )
    (comp (ref "C3866")
      (value "*")
      (footprint "C0201")
      (description "cap,100.00nF,+/-10%,10V,X5R,C0201")
      (fields
        (field (name "VOLTAGE") "10V")
        (field (name "PCB FOOTPRINT") "C0201")
        (field (name "DIELECTRIC") "X5R")
        (field (name "TOLERANCE") "10%")
        (field (name "MANUFACTURER") "TDK")
        (field (name "ALTIUM_UNNAMED_1") "100nF")
        (field (name "CREATED BY") "JJJ")
      )
      (libsource (lib "*") (part "CAP NP"))
    )
    (comp (ref "C3867")
      (value "*")
      (footprint "C0201")
      (description "cap,100.00nF,+/-10%,10V,X5R,C0201")
      (fields
        (field (name "VOLTAGE") "10V")
        (field (name "PCB FOOTPRINT") "C0201")
        (field (name "DIELECTRIC") "X5R")
        (field (name "MANUFACTURER") "TDK")
        (field (name "TOLERANCE") "10%")
        (field (name "ALTIUM_UNNAMED_1") "100nF")
        (field (name "CREATED BY") "JJJ")
      )
      (libsource (lib "*") (part "CAP NP"))
    )
    (comp (ref "C3868")
      (value "*")
      (footprint "C0201")
      (description "cap,100.00nF,+/-10%,10V,X5R,C0201")
      (fields
        (field (name "VOLTAGE") "10V")
        (field (name "PCB FOOTPRINT") "C0201")
        (field (name "DIELECTRIC") "X5R")
        (field (name "TOLERANCE") "10%")
        (field (name "MANUFACTURER") "TDK")
        (field (name "ALTIUM_UNNAMED_1") "100nF")
        (field (name "CREATED BY") "JJJ")
      )
      (libsource (lib "*") (part "CAP NP"))
    )
    (comp (ref "C3869")
      (value "*")
      (footprint "C0603")
      (description "cap,22.00uF,+/-20%,6.3V,X5R,C0603")
      (fields
        (field (name "VOLTAGE") "6.3V")
        (field (name "PCB FOOTPRINT") "C0603")
        (field (name "DIELECTRIC") "X5R")
        (field (name "MANUFACTURER") "TDK")
        (field (name "TOLERANCE") "20%")
        (field (name "ALTIUM_UNNAMED_1") "22uF")
        (field (name "CREATED BY") "JJJ")
      )
      (libsource (lib "*") (part "CAP NP"))
    )
    (comp (ref "C3870")
      (value "*")
      (footprint "C0603")
      (description "cap,10.00uF,+/-10%,10V,X5R,C0603")
      (fields
        (field (name "VOLTAGE") "10V")
        (field (name "PCB FOOTPRINT") "C0603")
        (field (name "DIELECTRIC") "X5R")
        (field (name "TOLERANCE") "10%")
        (field (name "MANUFACTURER") "TDK")
        (field (name "ALTIUM_UNNAMED_1") "10uF")
        (field (name "CREATED BY") "JJJ")
      )
      (libsource (lib "*") (part "CAP NP"))
    )
    (comp (ref "C3871")
      (value "*")
      (footprint "C0603")
      (description "cap,10.00uF,+/-10%,10V,X5R,C0603")
      (fields
        (field (name "VOLTAGE") "10V")
        (field (name "PCB FOOTPRINT") "C0603")
        (field (name "DIELECTRIC") "X5R")
        (field (name "MANUFACTURER") "TDK")
        (field (name "TOLERANCE") "10%")
        (field (name "ALTIUM_UNNAMED_1") "10uF")
        (field (name "CREATED BY") "JJJ")
      )
      (libsource (lib "*") (part "CAP NP"))
    )
    (comp (ref "C3872")
      (value "*")
      (footprint "C0402")
      (description "cap,1.00uF,+/-10%,6.3V,X5R,C0402")
      (fields
        (field (name "VOLTAGE") "6.3V")
        (field (name "PCB FOOTPRINT") "C0402")
        (field (name "DIELECTRIC") "X5R")
        (field (name "MANUFACTURER") "TDK")
        (field (name "TOLERANCE") "10%")
        (field (name "ALTIUM_UNNAMED_1") "1uF")
        (field (name "CREATED BY") "JJJ")
      )
      (libsource (lib "*") (part "CAP NP"))
    )
    (comp (ref "C3873")
      (value "*")
      (footprint "C0402")
      (description "cap,1.00uF,+/-10%,6.3V,X5R,C0402")
      (fields
        (field (name "VOLTAGE") "6.3V")
        (field (name "PCB FOOTPRINT") "C0402")
        (field (name "DIELECTRIC") "X5R")
        (field (name "MANUFACTURER") "TDK")
        (field (name "TOLERANCE") "10%")
        (field (name "ALTIUM_UNNAMED_1") "1uF")
        (field (name "CREATED BY") "JJJ")
      )
      (libsource (lib "*") (part "CAP NP"))
    )
    (comp (ref "C3874")
      (value "*")
      (footprint "C0201")
      (description "cap,100.00nF,+/-10%,10V,X5R,C0201")
      (fields
        (field (name "VOLTAGE") "10V")
        (field (name "PCB FOOTPRINT") "C0201")
        (field (name "DIELECTRIC") "X5R")
        (field (name "MANUFACTURER") "TDK")
        (field (name "TOLERANCE") "10%")
        (field (name "ALTIUM_UNNAMED_1") "100nF")
        (field (name "CREATED BY") "JJJ")
      )
      (libsource (lib "*") (part "CAP NP"))
    )
    (comp (ref "C3875")
      (value "*")
      (footprint "C0201")
      (description "cap,100.00nF,+/-10%,10V,X5R,C0201")
      (fields
        (field (name "VOLTAGE") "10V")
        (field (name "PCB FOOTPRINT") "C0201")
        (field (name "DIELECTRIC") "X5R")
        (field (name "MANUFACTURER") "TDK")
        (field (name "TOLERANCE") "10%")
        (field (name "ALTIUM_UNNAMED_1") "100nF")
        (field (name "CREATED BY") "JJJ")
      )
      (libsource (lib "*") (part "CAP NP"))
    )
    (comp (ref "C3876")
      (value "*")
      (footprint "C0201")
      (description "cap,100.00nF,+/-10%,10V,X5R,C0201")
      (fields
        (field (name "VOLTAGE") "10V")
        (field (name "PCB FOOTPRINT") "C0201")
        (field (name "DIELECTRIC") "X5R")
        (field (name "MANUFACTURER") "TDK")
        (field (name "TOLERANCE") "10%")
        (field (name "ALTIUM_UNNAMED_1") "100nF")
        (field (name "CREATED BY") "JJJ")
      )
      (libsource (lib "*") (part "CAP NP"))
    )
    (comp (ref "C3877")
      (value "*")
      (footprint "C0201")
      (description "cap,100.00nF,+/-10%,10V,X5R,C0201")
      (fields
        (field (name "VOLTAGE") "10V")
        (field (name "PCB FOOTPRINT") "C0201")
        (field (name "DIELECTRIC") "X5R")
        (field (name "TOLERANCE") "10%")
        (field (name "MANUFACTURER") "TDK")
        (field (name "ALTIUM_UNNAMED_1") "100nF")
        (field (name "CREATED BY") "JJJ")
      )
      (libsource (lib "*") (part "CAP NP"))
    )
    (comp (ref "C3878")
      (value "*")
      (footprint "C0201")
      (description "cap,100.00nF,+/-10%,10V,X5R,C0201")
      (fields
        (field (name "VOLTAGE") "10V")
        (field (name "PCB FOOTPRINT") "C0201")
        (field (name "DIELECTRIC") "X5R")
        (field (name "TOLERANCE") "10%")
        (field (name "MANUFACTURER") "TDK")
        (field (name "ALTIUM_UNNAMED_1") "100nF")
        (field (name "CREATED BY") "JJJ")
      )
      (libsource (lib "*") (part "CAP NP"))
    )
    (comp (ref "C3879")
      (value "*")
      (footprint "C0201")
      (description "cap,100.00nF,+/-10%,10V,X5R,C0201")
      (fields
        (field (name "VOLTAGE") "10V")
        (field (name "PCB FOOTPRINT") "C0201")
        (field (name "DIELECTRIC") "X5R")
        (field (name "TOLERANCE") "10%")
        (field (name "MANUFACTURER") "TDK")
        (field (name "ALTIUM_UNNAMED_1") "100nF")
        (field (name "CREATED BY") "JJJ")
      )
      (libsource (lib "*") (part "CAP NP"))
    )
    (comp (ref "C3880")
      (value "*")
      (footprint "C0201")
      (description "cap,100.00nF,+/-10%,10V,X5R,C0201")
      (fields
        (field (name "VOLTAGE") "10V")
        (field (name "PCB FOOTPRINT") "C0201")
        (field (name "DIELECTRIC") "X5R")
        (field (name "MANUFACTURER") "TDK")
        (field (name "TOLERANCE") "10%")
        (field (name "ALTIUM_UNNAMED_1") "100nF")
        (field (name "CREATED BY") "JJJ")
      )
      (libsource (lib "*") (part "CAP NP"))
    )
    (comp (ref "C3881")
      (value "*")
      (footprint "C0201")
      (description "cap,100.00nF,+/-10%,10V,X5R,C0201")
      (fields
        (field (name "VOLTAGE") "10V")
        (field (name "PCB FOOTPRINT") "C0201")
        (field (name "DIELECTRIC") "X5R")
        (field (name "TOLERANCE") "10%")
        (field (name "MANUFACTURER") "TDK")
        (field (name "ALTIUM_UNNAMED_1") "100nF")
        (field (name "CREATED BY") "JJJ")
      )
      (libsource (lib "*") (part "CAP NP"))
    )
    (comp (ref "C3882")
      (value "*")
      (footprint "C0201")
      (description "cap,100.00nF,+/-10%,10V,X5R,C0201")
      (fields
        (field (name "VOLTAGE") "10V")
        (field (name "PCB FOOTPRINT") "C0201")
        (field (name "DIELECTRIC") "X5R")
        (field (name "TOLERANCE") "10%")
        (field (name "MANUFACTURER") "TDK")
        (field (name "ALTIUM_UNNAMED_1") "100nF")
        (field (name "CREATED BY") "JJJ")
      )
      (libsource (lib "*") (part "CAP NP"))
    )
    (comp (ref "C3883")
      (value "*")
      (footprint "C0201")
      (description "cap,100.00nF,+/-10%,10V,X5R,C0201")
      (fields
        (field (name "VOLTAGE") "10V")
        (field (name "PCB FOOTPRINT") "C0201")
        (field (name "DIELECTRIC") "X5R")
        (field (name "MANUFACTURER") "TDK")
        (field (name "TOLERANCE") "10%")
        (field (name "ALTIUM_UNNAMED_1") "100nF")
        (field (name "CREATED BY") "JJJ")
      )
      (libsource (lib "*") (part "CAP NP"))
    )
    (comp (ref "C3884")
      (value "*")
      (footprint "C0201")
      (description "cap,100.00nF,+/-10%,10V,X5R,C0201")
      (fields
        (field (name "VOLTAGE") "10V")
        (field (name "PCB FOOTPRINT") "C0201")
        (field (name "DIELECTRIC") "X5R")
        (field (name "TOLERANCE") "10%")
        (field (name "MANUFACTURER") "TDK")
        (field (name "ALTIUM_UNNAMED_1") "100nF")
        (field (name "CREATED BY") "JJJ")
      )
      (libsource (lib "*") (part "CAP NP"))
    )
    (comp (ref "C3885")
      (value "*")
      (footprint "C0201")
      (description "cap,100.00nF,+/-10%,10V,X5R,C0201")
      (fields
        (field (name "VOLTAGE") "10V")
        (field (name "PCB FOOTPRINT") "C0201")
        (field (name "DIELECTRIC") "X5R")
        (field (name "MANUFACTURER") "TDK")
        (field (name "TOLERANCE") "10%")
        (field (name "ALTIUM_UNNAMED_1") "100nF")
        (field (name "CREATED BY") "JJJ")
      )
      (libsource (lib "*") (part "CAP NP"))
    )
    (comp (ref "C3886")
      (value "*")
      (footprint "C0201")
      (description "cap,100.00nF,+/-10%,10V,X5R,C0201")
      (fields
        (field (name "VOLTAGE") "10V")
        (field (name "PCB FOOTPRINT") "C0201")
        (field (name "DIELECTRIC") "X5R")
        (field (name "MANUFACTURER") "TDK")
        (field (name "TOLERANCE") "10%")
        (field (name "ALTIUM_UNNAMED_1") "100nF")
        (field (name "CREATED BY") "JJJ")
      )
      (libsource (lib "*") (part "CAP NP"))
    )
    (comp (ref "C3887")
      (value "*")
      (footprint "C0201")
      (description "cap,100.00nF,+/-10%,10V,X5R,C0201")
      (fields
        (field (name "VOLTAGE") "10V")
        (field (name "PCB FOOTPRINT") "C0201")
        (field (name "DIELECTRIC") "X5R")
        (field (name "MANUFACTURER") "TDK")
        (field (name "TOLERANCE") "10%")
        (field (name "ALTIUM_UNNAMED_1") "100nF")
        (field (name "CREATED BY") "JJJ")
      )
      (libsource (lib "*") (part "CAP NP"))
    )
    (comp (ref "C3888")
      (value "*")
      (footprint "C0201")
      (description "cap,1.00nF,+/-10%,25V,X5R,C0201")
      (fields
        (field (name "VOLTAGE") "25V")
        (field (name "PCB FOOTPRINT") "C0201")
        (field (name "DIELECTRIC") "X5R")
        (field (name "MANUFACTURER") "TDK")
        (field (name "TOLERANCE") "10%")
        (field (name "OPTION") "DNP")
        (field (name "ALTIUM_UNNAMED_1") "1nF")
        (field (name "CREATED BY") "JJJ")
      )
      (libsource (lib "*") (part "CAP NP"))
    )
    (comp (ref "R3800")
      (value "*")
      (footprint "R0402")
      (description "НЁУГєсД¤µзЧи,0R,+/-5%,R0603,1/10W.")
      (fields
        (field (name "PCB FOOTPRINT") "R0603")
        (field (name "TOLERANCE") "5%")
        (field (name "MANUFACTURER") "YAGEO")
        (field (name "OPTION") "DNP")
        (field (name "ALTIUM_UNNAMED_1") "0R")
        (field (name "CREATED BY") "YTL")
      )
      (libsource (lib "*") (part "RESISTOR_Dup1"))
    )
    (comp (ref "R3801")
      (value "*")
      (footprint "R0402")
      (description "НЁУГєсД¤µзЧи,49R9,+/-1%,R0201,1/20W.")
      (fields
        (field (name "PCB FOOTPRINT") "R0201")
        (field (name "TOLERANCE") "1%")
        (field (name "MANUFACTURER") "YAGEO")
        (field (name "ALTIUM_UNNAMED_1") "49.9R")
        (field (name "CREATED BY") "YTL")
      )
      (libsource (lib "*") (part "RESISTOR_Dup1"))
    )
    (comp (ref "R3802")
      (value "*")
      (footprint "R0402")
      (description "НЁУГєсД¤µзЧи,49R9,+/-1%,R0201,1/20W.")
      (fields
        (field (name "PCB FOOTPRINT") "R0201")
        (field (name "TOLERANCE") "1%")
        (field (name "MANUFACTURER") "YAGEO")
        (field (name "ALTIUM_UNNAMED_1") "49.9R")
        (field (name "CREATED BY") "YTL")
      )
      (libsource (lib "*") (part "RESISTOR_Dup1"))
    )
    (comp (ref "R3803")
      (value "*")
      (footprint "R0402")
      (description "НЁУГєсД¤µзЧи,0R,+/-5%,R0603,1/10W.")
      (fields
        (field (name "PCB FOOTPRINT") "R0603")
        (field (name "TOLERANCE") "5%")
        (field (name "MANUFACTURER") "YAGEO")
        (field (name "ALTIUM_UNNAMED_1") "0R")
        (field (name "CREATED BY") "YTL")
      )
      (libsource (lib "*") (part "RESISTOR_Dup1"))
    )
    (comp (ref "R3804")
      (value "*")
      (footprint "R0402")
      (description "НЁУГєсД¤µзЧи,49R9,+/-1%,R0201,1/20W.")
      (fields
        (field (name "PCB FOOTPRINT") "R0201")
        (field (name "TOLERANCE") "1%")
        (field (name "MANUFACTURER") "YAGEO")
        (field (name "ALTIUM_UNNAMED_1") "49.9R")
        (field (name "CREATED BY") "YTL")
      )
      (libsource (lib "*") (part "RESISTOR_Dup1"))
    )
    (comp (ref "R3805")
      (value "*")
      (footprint "R0402")
      (description "НЁУГєсД¤µзЧи,49R9,+/-1%,R0201,1/20W.")
      (fields
        (field (name "PCB FOOTPRINT") "R0201")
        (field (name "TOLERANCE") "1%")
        (field (name "MANUFACTURER") "YAGEO")
        (field (name "ALTIUM_UNNAMED_1") "49.9R")
        (field (name "CREATED BY") "YTL")
      )
      (libsource (lib "*") (part "RESISTOR_Dup1"))
    )
    (comp (ref "R3806")
      (value "*")
      (footprint "R0402")
      (description "НЁУГєсД¤µзЧи,10K,+/-5%,R0201,1/20W.")
      (fields
        (field (name "PCB FOOTPRINT") "R0201")
        (field (name "TOLERANCE") "5%")
        (field (name "MANUFACTURER") "YAGEO")
        (field (name "ALTIUM_UNNAMED_1") "10K")
        (field (name "CREATED BY") "YTL")
      )
      (libsource (lib "*") (part "RESISTOR_Dup1"))
    )
    (comp (ref "R3807")
      (value "*")
      (footprint "R0402")
      (description "НЁУГєсД¤µзЧи,10K,+/-5%,R0201,1/20W.")
      (fields
        (field (name "PCB FOOTPRINT") "R0201")
        (field (name "TOLERANCE") "5%")
        (field (name "MANUFACTURER") "YAGEO")
        (field (name "ALTIUM_UNNAMED_1") "10K")
        (field (name "CREATED BY") "YTL")
      )
      (libsource (lib "*") (part "RESISTOR_Dup1"))
    )
    (comp (ref "R3808")
      (value "*")
      (footprint "R0402")
      (description "НЁУГєсД¤µзЧи,0R,+/-5%,R0805,1/8W.")
      (fields
        (field (name "PCB FOOTPRINT") "R0805")
        (field (name "TOLERANCE") "5%")
        (field (name "MANUFACTURER") "YAGEO")
        (field (name "ALTIUM_UNNAMED_1") "0R")
        (field (name "CREATED BY") "YTL")
      )
      (libsource (lib "*") (part "RESISTOR_Dup1"))
    )
    (comp (ref "R3809")
      (value "*")
      (footprint "R0402")
      (description "НЁУГєсД¤µзЧи,240R,+/-1%,R0201,1/20W.")
      (fields
        (field (name "PCB FOOTPRINT") "R0201")
        (field (name "TOLERANCE") "1%")
        (field (name "MANUFACTURER") "YAGEO")
        (field (name "ALTIUM_UNNAMED_1") "240R")
        (field (name "CREATED BY") "YTL")
      )
      (libsource (lib "*") (part "RESISTOR_Dup1"))
    )
    (comp (ref "R3810")
      (value "*")
      (footprint "R0402")
      (description "НЁУГєсД¤µзЧи,240R,+/-1%,R0201,1/20W.")
      (fields
        (field (name "PCB FOOTPRINT") "R0201")
        (field (name "TOLERANCE") "1%")
        (field (name "MANUFACTURER") "YAGEO")
        (field (name "ALTIUM_UNNAMED_1") "240R")
        (field (name "CREATED BY") "YTL")
      )
      (libsource (lib "*") (part "RESISTOR_Dup1"))
    )
    (comp (ref "R3811")
      (value "*")
      (footprint "R0402")
      (description "НЁУГєсД¤µзЧи,0R,+/-5%,R0805,1/8W.")
      (fields
        (field (name "PCB FOOTPRINT") "R0805")
        (field (name "TOLERANCE") "5%")
        (field (name "OPTION") "DNP")
        (field (name "MANUFACTURER") "YAGEO")
        (field (name "ALTIUM_UNNAMED_1") "0R")
        (field (name "CREATED BY") "YTL")
      )
      (libsource (lib "*") (part "RESISTOR_Dup1"))
    )
    (comp (ref "R3812")
      (value "*")
      (footprint "R0402")
      (description "НЁУГєсД¤µзЧи,49R9,+/-1%,R0201,1/20W.")
      (fields
        (field (name "PCB FOOTPRINT") "R0201")
        (field (name "TOLERANCE") "1%")
        (field (name "MANUFACTURER") "YAGEO")
        (field (name "ALTIUM_UNNAMED_1") "49.9R")
        (field (name "CREATED BY") "YTL")
      )
      (libsource (lib "*") (part "RESISTOR_Dup1"))
    )
    (comp (ref "R3813")
      (value "*")
      (footprint "R0402")
      (description "НЁУГєсД¤µзЧи,49R9,+/-1%,R0201,1/20W.")
      (fields
        (field (name "PCB FOOTPRINT") "R0201")
        (field (name "TOLERANCE") "1%")
        (field (name "MANUFACTURER") "YAGEO")
        (field (name "ALTIUM_UNNAMED_1") "49.9R")
        (field (name "CREATED BY") "YTL")
      )
      (libsource (lib "*") (part "RESISTOR_Dup1"))
    )
    (comp (ref "R3814")
      (value "*")
      (footprint "R0402")
      (description "НЁУГєсД¤µзЧи,49R9,+/-1%,R0201,1/20W.")
      (fields
        (field (name "PCB FOOTPRINT") "R0201")
        (field (name "TOLERANCE") "1%")
        (field (name "MANUFACTURER") "YAGEO")
        (field (name "ALTIUM_UNNAMED_1") "49.9R")
        (field (name "CREATED BY") "YTL")
      )
      (libsource (lib "*") (part "RESISTOR_Dup1"))
    )
    (comp (ref "R3815")
      (value "*")
      (footprint "R0402")
      (description "НЁУГєсД¤µзЧи,49R9,+/-1%,R0201,1/20W.")
      (fields
        (field (name "PCB FOOTPRINT") "R0201")
        (field (name "TOLERANCE") "1%")
        (field (name "MANUFACTURER") "YAGEO")
        (field (name "ALTIUM_UNNAMED_1") "49.9R")
        (field (name "CREATED BY") "YTL")
      )
      (libsource (lib "*") (part "RESISTOR_Dup1"))
    )
    (comp (ref "R3816")
      (value "*")
      (footprint "R0402")
      (description "НЁУГєсД¤µзЧи,10K,+/-5%,R0201,1/20W.")
      (fields
        (field (name "PCB FOOTPRINT") "R0201")
        (field (name "TOLERANCE") "5%")
        (field (name "MANUFACTURER") "YAGEO")
        (field (name "ALTIUM_UNNAMED_1") "10K")
        (field (name "CREATED BY") "YTL")
      )
      (libsource (lib "*") (part "RESISTOR_Dup1"))
    )
    (comp (ref "R3817")
      (value "*")
      (footprint "R0402")
      (description "НЁУГєсД¤µзЧи,10K,+/-5%,R0201,1/20W.")
      (fields
        (field (name "PCB FOOTPRINT") "R0201")
        (field (name "TOLERANCE") "5%")
        (field (name "MANUFACTURER") "YAGEO")
        (field (name "ALTIUM_UNNAMED_1") "10K")
        (field (name "CREATED BY") "YTL")
      )
      (libsource (lib "*") (part "RESISTOR_Dup1"))
    )
    (comp (ref "R3818")
      (value "*")
      (footprint "R0402")
      (description "НЁУГєсД¤µзЧи,240R,+/-1%,R0201,1/20W.")
      (fields
        (field (name "PCB FOOTPRINT") "R0201")
        (field (name "TOLERANCE") "1%")
        (field (name "MANUFACTURER") "YAGEO")
        (field (name "ALTIUM_UNNAMED_1") "240R")
        (field (name "CREATED BY") "YTL")
      )
      (libsource (lib "*") (part "RESISTOR_Dup1"))
    )
    (comp (ref "R3819")
      (value "*")
      (footprint "R0402")
      (description "НЁУГєсД¤µзЧи,240R,+/-1%,R0201,1/20W.")
      (fields
        (field (name "PCB FOOTPRINT") "R0201")
        (field (name "TOLERANCE") "1%")
        (field (name "MANUFACTURER") "YAGEO")
        (field (name "ALTIUM_UNNAMED_1") "240R")
        (field (name "CREATED BY") "YTL")
      )
      (libsource (lib "*") (part "RESISTOR_Dup1"))
    )
    (comp (ref "U3800")
      (value "*")
      (footprint "BGA200_15R00X10R00X0R90")
      (fields
        (field (name "PCB FOOTPRINT") "BGA200_15R00X10R00X0R90")
        (field (name "ALTIUM_UNNAMED_1") "LPDDR4_200P")
      )
      (libsource (lib "*") (part "LPDDR4_200P"))
    )
    (comp (ref "U3801")
      (value "*")
      (footprint "BGA200_15R00X10R00X0R90")
      (fields
        (field (name "PCB FOOTPRINT") "BGA200_15R00X10R00X0R90")
        (field (name "ALTIUM_UNNAMED_1") "LPDDR4_200P")
      )
      (libsource (lib "*") (part "LPDDR4_200P"))
    )
  )
  (nets
    (net (code "1") (name "/DDR_CH0_LP4{slash}4X_CKE0_A") (class "Default")
      (node (ref "R3801") (pin "2") (pinfunction "2_2") (pintype "passive"))
      (node (ref "U3800") (pin "J4") (pinfunction "CKE0_a_J4") (pintype "passive"))
    )
    (net (code "2") (name "/DDR_CH0_LP4{slash}4X_CKE0_B") (class "Default")
      (node (ref "R3804") (pin "2") (pinfunction "2_2") (pintype "passive"))
      (node (ref "U3800") (pin "P4") (pinfunction "CKE0_b_P4") (pintype "passive"))
    )
    (net (code "3") (name "/DDR_CH0_LP4{slash}4X_CKE1_A") (class "Default")
      (node (ref "R3802") (pin "2") (pinfunction "2_2") (pintype "passive"))
      (node (ref "U3800") (pin "J5") (pinfunction "CKE1_a_J5") (pintype "passive"))
    )
    (net (code "4") (name "/DDR_CH0_LP4{slash}4X_CKE1_B") (class "Default")
      (node (ref "R3805") (pin "2") (pinfunction "2_2") (pintype "passive"))
      (node (ref "U3800") (pin "P5") (pinfunction "CKE1_b_P5") (pintype "passive"))
    )
    (net (code "5") (name "/DDR_CH1_LP4{slash}4X_CKE0_C") (class "Default")
      (node (ref "R3812") (pin "2") (pinfunction "2_2") (pintype "passive"))
      (node (ref "U3801") (pin "J4") (pinfunction "CKE0_a_J4") (pintype "passive"))
    )
    (net (code "6") (name "/DDR_CH1_LP4{slash}4X_CKE0_D") (class "Default")
      (node (ref "R3814") (pin "2") (pinfunction "2_2") (pintype "passive"))
      (node (ref "U3801") (pin "P4") (pinfunction "CKE0_b_P4") (pintype "passive"))
    )
    (net (code "7") (name "/DDR_CH1_LP4{slash}4X_CKE1_C") (class "Default")
      (node (ref "R3813") (pin "2") (pinfunction "2_2") (pintype "passive"))
      (node (ref "U3801") (pin "J5") (pinfunction "CKE1_a_J5") (pintype "passive"))
    )
    (net (code "8") (name "/DDR_CH1_LP4{slash}4X_CKE1_D") (class "Default")
      (node (ref "R3815") (pin "2") (pinfunction "2_2") (pintype "passive"))
      (node (ref "U3801") (pin "P5") (pinfunction "CKE1_b_P5") (pintype "passive"))
    )
    (net (code "9") (name "DDR_CH0_A0_A") (class "Default")
      (node (ref "U3800") (pin "H2") (pinfunction "CA0_a_H2") (pintype "passive"))
    )
    (net (code "10") (name "DDR_CH0_A0_B") (class "Default")
      (node (ref "U3800") (pin "R2") (pinfunction "CA0_b_R2") (pintype "passive"))
    )
    (net (code "11") (name "DDR_CH0_A1_A") (class "Default")
      (node (ref "U3800") (pin "J2") (pinfunction "CA1_a_J2") (pintype "passive"))
    )
    (net (code "12") (name "DDR_CH0_A1_B") (class "Default")
      (node (ref "U3800") (pin "P2") (pinfunction "CA1_b_P2") (pintype "passive"))
    )
    (net (code "13") (name "DDR_CH0_A2_A") (class "Default")
      (node (ref "U3800") (pin "H9") (pinfunction "CA2_a_H9") (pintype "passive"))
    )
    (net (code "14") (name "DDR_CH0_A2_B") (class "Default")
      (node (ref "U3800") (pin "R9") (pinfunction "CA2_b_R9") (pintype "passive"))
    )
    (net (code "15") (name "DDR_CH0_A3_A") (class "Default")
      (node (ref "U3800") (pin "H10") (pinfunction "CA3_a_H10") (pintype "passive"))
    )
    (net (code "16") (name "DDR_CH0_A3_B") (class "Default")
      (node (ref "U3800") (pin "R10") (pinfunction "CA3_b_R10") (pintype "passive"))
    )
    (net (code "17") (name "DDR_CH0_A4_A") (class "Default")
      (node (ref "U3800") (pin "H11") (pinfunction "CA4_a_H11") (pintype "passive"))
    )
    (net (code "18") (name "DDR_CH0_A4_B") (class "Default")
      (node (ref "U3800") (pin "R11") (pinfunction "CA4_b_R11") (pintype "passive"))
    )
    (net (code "19") (name "DDR_CH0_A5_A") (class "Default")
      (node (ref "U3800") (pin "J11") (pinfunction "CA5_a_J11") (pintype "passive"))
    )
    (net (code "20") (name "DDR_CH0_A5_B") (class "Default")
      (node (ref "U3800") (pin "P11") (pinfunction "CA5_B_P11") (pintype "passive"))
    )
    (net (code "21") (name "DDR_CH0_CLKN_A") (class "Default")
      (node (ref "U3800") (pin "J9") (pinfunction "CK_c_a_J9") (pintype "passive"))
    )
    (net (code "22") (name "DDR_CH0_CLKN_B") (class "Default")
      (node (ref "U3800") (pin "P9") (pinfunction "CK_c_b_P9") (pintype "passive"))
    )
    (net (code "23") (name "DDR_CH0_CLKP_A") (class "Default")
      (node (ref "U3800") (pin "J8") (pinfunction "CK_t_a_J8") (pintype "passive"))
    )
    (net (code "24") (name "DDR_CH0_CLKP_B") (class "Default")
      (node (ref "U3800") (pin "P8") (pinfunction "CK_t_b_P8") (pintype "passive"))
    )
    (net (code "25") (name "DDR_CH0_DM0_A") (class "Default")
      (node (ref "U3800") (pin "C3") (pinfunction "DMI0_a_C3") (pintype "passive"))
    )
    (net (code "26") (name "DDR_CH0_DM0_B") (class "Default")
      (node (ref "U3800") (pin "Y3") (pinfunction "DMI0_b_Y3") (pintype "passive"))
    )
    (net (code "27") (name "DDR_CH0_DM1_A") (class "Default")
      (node (ref "U3800") (pin "C10") (pinfunction "DMI1_a_C10") (pintype "passive"))
    )
    (net (code "28") (name "DDR_CH0_DM1_B") (class "Default")
      (node (ref "U3800") (pin "Y10") (pinfunction "DMI1_b_Y10") (pintype "passive"))
    )
    (net (code "29") (name "DDR_CH0_DQ0_A") (class "Default")
      (node (ref "U3800") (pin "B2") (pinfunction "DQ0_a_B2") (pintype "passive"))
    )
    (net (code "30") (name "DDR_CH0_DQ0_B") (class "Default")
      (node (ref "U3800") (pin "AA2") (pinfunction "DQ0_b_AA2") (pintype "passive"))
    )
    (net (code "31") (name "DDR_CH0_DQ1_A") (class "Default")
      (node (ref "U3800") (pin "C2") (pinfunction "DQ1_a_C2") (pintype "passive"))
    )
    (net (code "32") (name "DDR_CH0_DQ1_B") (class "Default")
      (node (ref "U3800") (pin "Y2") (pinfunction "DQ1_b_Y2") (pintype "passive"))
    )
    (net (code "33") (name "DDR_CH0_DQ2_A") (class "Default")
      (node (ref "U3800") (pin "E2") (pinfunction "DQ2_a_E2") (pintype "passive"))
    )
    (net (code "34") (name "DDR_CH0_DQ2_B") (class "Default")
      (node (ref "U3800") (pin "V2") (pinfunction "DQ2_b_V2") (pintype "passive"))
    )
    (net (code "35") (name "DDR_CH0_DQ3_A") (class "Default")
      (node (ref "U3800") (pin "F2") (pinfunction "DQ3_a_F2") (pintype "passive"))
    )
    (net (code "36") (name "DDR_CH0_DQ3_B") (class "Default")
      (node (ref "U3800") (pin "U2") (pinfunction "DQ3_b_U2") (pintype "passive"))
    )
    (net (code "37") (name "DDR_CH0_DQ4_A") (class "Default")
      (node (ref "U3800") (pin "F4") (pinfunction "DQ4_a_F4") (pintype "passive"))
    )
    (net (code "38") (name "DDR_CH0_DQ4_B") (class "Default")
      (node (ref "U3800") (pin "U4") (pinfunction "DQ4_b_U4") (pintype "passive"))
    )
    (net (code "39") (name "DDR_CH0_DQ5_A") (class "Default")
      (node (ref "U3800") (pin "E4") (pinfunction "DQ5_a_E4") (pintype "passive"))
    )
    (net (code "40") (name "DDR_CH0_DQ5_B") (class "Default")
      (node (ref "U3800") (pin "V4") (pinfunction "DQ5_b_V4") (pintype "passive"))
    )
    (net (code "41") (name "DDR_CH0_DQ6_A") (class "Default")
      (node (ref "U3800") (pin "C4") (pinfunction "DQ6_a_C4") (pintype "passive"))
    )
    (net (code "42") (name "DDR_CH0_DQ6_B") (class "Default")
      (node (ref "U3800") (pin "Y4") (pinfunction "DQ6_b_Y4") (pintype "passive"))
    )
    (net (code "43") (name "DDR_CH0_DQ7_A") (class "Default")
      (node (ref "U3800") (pin "B4") (pinfunction "DQ7_a_B4") (pintype "passive"))
    )
    (net (code "44") (name "DDR_CH0_DQ7_B") (class "Default")
      (node (ref "U3800") (pin "AA4") (pinfunction "DQ7_b_AA4") (pintype "passive"))
    )
    (net (code "45") (name "DDR_CH0_DQ8_A") (class "Default")
      (node (ref "U3800") (pin "B11") (pinfunction "DQ8_a_B11") (pintype "passive"))
    )
    (net (code "46") (name "DDR_CH0_DQ8_B") (class "Default")
      (node (ref "U3800") (pin "AA11") (pinfunction "DQ8_b_AA11") (pintype "passive"))
    )
    (net (code "47") (name "DDR_CH0_DQ9_A") (class "Default")
      (node (ref "U3800") (pin "C11") (pinfunction "DQ9_a_C11") (pintype "passive"))
    )
    (net (code "48") (name "DDR_CH0_DQ9_B") (class "Default")
      (node (ref "U3800") (pin "Y11") (pinfunction "DQ9_b_Y11") (pintype "passive"))
    )
    (net (code "49") (name "DDR_CH0_DQ10_A") (class "Default")
      (node (ref "U3800") (pin "E11") (pinfunction "DQ10_a_E11") (pintype "passive"))
    )
    (net (code "50") (name "DDR_CH0_DQ10_B") (class "Default")
      (node (ref "U3800") (pin "V11") (pinfunction "DQ10_b_V11") (pintype "passive"))
    )
    (net (code "51") (name "DDR_CH0_DQ11_A") (class "Default")
      (node (ref "U3800") (pin "F11") (pinfunction "DQ11_a_F11") (pintype "passive"))
    )
    (net (code "52") (name "DDR_CH0_DQ11_B") (class "Default")
      (node (ref "U3800") (pin "U11") (pinfunction "DQ11_b_U11") (pintype "passive"))
    )
    (net (code "53") (name "DDR_CH0_DQ12_A") (class "Default")
      (node (ref "U3800") (pin "F9") (pinfunction "DQ12_a_F9") (pintype "passive"))
    )
    (net (code "54") (name "DDR_CH0_DQ12_B") (class "Default")
      (node (ref "U3800") (pin "U9") (pinfunction "DQ12_b_U9") (pintype "passive"))
    )
    (net (code "55") (name "DDR_CH0_DQ13_A") (class "Default")
      (node (ref "U3800") (pin "E9") (pinfunction "DQ13_a_E9") (pintype "passive"))
    )
    (net (code "56") (name "DDR_CH0_DQ13_B") (class "Default")
      (node (ref "U3800") (pin "V9") (pinfunction "DQ13_b_V9") (pintype "passive"))
    )
    (net (code "57") (name "DDR_CH0_DQ14_A") (class "Default")
      (node (ref "U3800") (pin "C9") (pinfunction "DQ14_a_C9") (pintype "passive"))
    )
    (net (code "58") (name "DDR_CH0_DQ14_B") (class "Default")
      (node (ref "U3800") (pin "Y9") (pinfunction "DQ14_b_Y9") (pintype "passive"))
    )
    (net (code "59") (name "DDR_CH0_DQ15_A") (class "Default")
      (node (ref "U3800") (pin "B9") (pinfunction "DQ15_a_B9") (pintype "passive"))
    )
    (net (code "60") (name "DDR_CH0_DQ15_B") (class "Default")
      (node (ref "U3800") (pin "AA9") (pinfunction "DQ15_b_AA9") (pintype "passive"))
    )
    (net (code "61") (name "DDR_CH0_DQS0N_A") (class "Default")
      (node (ref "U3800") (pin "E3") (pinfunction "DQS0_c_a_E3") (pintype "passive"))
    )
    (net (code "62") (name "DDR_CH0_DQS0N_B") (class "Default")
      (node (ref "U3800") (pin "V3") (pinfunction "DQS0_c_b_V3") (pintype "passive"))
    )
    (net (code "63") (name "DDR_CH0_DQS0P_A") (class "Default")
      (node (ref "U3800") (pin "D3") (pinfunction "DQS0_t_a_D3") (pintype "passive"))
    )
    (net (code "64") (name "DDR_CH0_DQS0P_B") (class "Default")
      (node (ref "U3800") (pin "W3") (pinfunction "DQS0_t_b_W3") (pintype "passive"))
    )
    (net (code "65") (name "DDR_CH0_DQS1N_A") (class "Default")
      (node (ref "U3800") (pin "E10") (pinfunction "DQS1_c_a_E10") (pintype "passive"))
    )
    (net (code "66") (name "DDR_CH0_DQS1N_B") (class "Default")
      (node (ref "U3800") (pin "V10") (pinfunction "DQS1_c_b_V10") (pintype "passive"))
    )
    (net (code "67") (name "DDR_CH0_DQS1P_A") (class "Default")
      (node (ref "U3800") (pin "D10") (pinfunction "DQS1_t_a_D10") (pintype "passive"))
    )
    (net (code "68") (name "DDR_CH0_DQS1P_B") (class "Default")
      (node (ref "U3800") (pin "W10") (pinfunction "DQS1_t_b_W10") (pintype "passive"))
    )
    (net (code "69") (name "DDR_CH0_LP4{slash}4X_CKE0{slash}LP5_CS0_A") (class "Default")
      (node (ref "R3801") (pin "1") (pinfunction "1_1") (pintype "passive"))
    )
    (net (code "70") (name "DDR_CH0_LP4{slash}4X_CKE0{slash}LP5_CS0_B") (class "Default")
      (node (ref "R3804") (pin "1") (pinfunction "1_1") (pintype "passive"))
    )
    (net (code "71") (name "DDR_CH0_LP4{slash}4X_CKE1{slash}LP5_CS1_A") (class "Default")
      (node (ref "R3802") (pin "1") (pinfunction "1_1") (pintype "passive"))
    )
    (net (code "72") (name "DDR_CH0_LP4{slash}4X_CKE1{slash}LP5_CS1_B") (class "Default")
      (node (ref "R3805") (pin "1") (pinfunction "1_1") (pintype "passive"))
    )
    (net (code "73") (name "DDR_CH0_LP4{slash}4X_CS0_A") (class "Default")
      (node (ref "U3800") (pin "H4") (pinfunction "CS0_a_H4") (pintype "passive"))
    )
    (net (code "74") (name "DDR_CH0_LP4{slash}4X_CS0_B") (class "Default")
      (node (ref "U3800") (pin "R4") (pinfunction "CS0_b_R4") (pintype "passive"))
    )
    (net (code "75") (name "DDR_CH0_LP4{slash}4X_CS1_A") (class "Default")
      (node (ref "U3800") (pin "H3") (pinfunction "CS1_a_H3") (pintype "passive"))
    )
    (net (code "76") (name "DDR_CH0_LP4{slash}4X_CS1_B") (class "Default")
      (node (ref "U3800") (pin "R3") (pinfunction "CS1_b_R3") (pintype "passive"))
    )
    (net (code "77") (name "DDR_CH1_A0_C") (class "Default")
      (node (ref "U3801") (pin "H2") (pinfunction "CA0_a_H2") (pintype "passive"))
    )
    (net (code "78") (name "DDR_CH1_A0_D") (class "Default")
      (node (ref "U3801") (pin "R2") (pinfunction "CA0_b_R2") (pintype "passive"))
    )
    (net (code "79") (name "DDR_CH1_A1_C") (class "Default")
      (node (ref "U3801") (pin "J2") (pinfunction "CA1_a_J2") (pintype "passive"))
    )
    (net (code "80") (name "DDR_CH1_A1_D") (class "Default")
      (node (ref "U3801") (pin "P2") (pinfunction "CA1_b_P2") (pintype "passive"))
    )
    (net (code "81") (name "DDR_CH1_A2_C") (class "Default")
      (node (ref "U3801") (pin "H9") (pinfunction "CA2_a_H9") (pintype "passive"))
    )
    (net (code "82") (name "DDR_CH1_A2_D") (class "Default")
      (node (ref "U3801") (pin "R9") (pinfunction "CA2_b_R9") (pintype "passive"))
    )
    (net (code "83") (name "DDR_CH1_A3_C") (class "Default")
      (node (ref "U3801") (pin "H10") (pinfunction "CA3_a_H10") (pintype "passive"))
    )
    (net (code "84") (name "DDR_CH1_A3_D") (class "Default")
      (node (ref "U3801") (pin "R10") (pinfunction "CA3_b_R10") (pintype "passive"))
    )
    (net (code "85") (name "DDR_CH1_A4_C") (class "Default")
      (node (ref "U3801") (pin "H11") (pinfunction "CA4_a_H11") (pintype "passive"))
    )
    (net (code "86") (name "DDR_CH1_A4_D") (class "Default")
      (node (ref "U3801") (pin "R11") (pinfunction "CA4_b_R11") (pintype "passive"))
    )
    (net (code "87") (name "DDR_CH1_A5_C") (class "Default")
      (node (ref "U3801") (pin "J11") (pinfunction "CA5_a_J11") (pintype "passive"))
    )
    (net (code "88") (name "DDR_CH1_A5_D") (class "Default")
      (node (ref "U3801") (pin "P11") (pinfunction "CA5_B_P11") (pintype "passive"))
    )
    (net (code "89") (name "DDR_CH1_CLKN_C") (class "Default")
      (node (ref "U3801") (pin "J9") (pinfunction "CK_c_a_J9") (pintype "passive"))
    )
    (net (code "90") (name "DDR_CH1_CLKN_D") (class "Default")
      (node (ref "U3801") (pin "P9") (pinfunction "CK_c_b_P9") (pintype "passive"))
    )
    (net (code "91") (name "DDR_CH1_CLKP_C") (class "Default")
      (node (ref "U3801") (pin "J8") (pinfunction "CK_t_a_J8") (pintype "passive"))
    )
    (net (code "92") (name "DDR_CH1_CLKP_D") (class "Default")
      (node (ref "U3801") (pin "P8") (pinfunction "CK_t_b_P8") (pintype "passive"))
    )
    (net (code "93") (name "DDR_CH1_DM0_C") (class "Default")
      (node (ref "U3801") (pin "C3") (pinfunction "DMI0_a_C3") (pintype "passive"))
    )
    (net (code "94") (name "DDR_CH1_DM0_D") (class "Default")
      (node (ref "U3801") (pin "Y3") (pinfunction "DMI0_b_Y3") (pintype "passive"))
    )
    (net (code "95") (name "DDR_CH1_DM1_C") (class "Default")
      (node (ref "U3801") (pin "C10") (pinfunction "DMI1_a_C10") (pintype "passive"))
    )
    (net (code "96") (name "DDR_CH1_DM1_D") (class "Default")
      (node (ref "U3801") (pin "Y10") (pinfunction "DMI1_b_Y10") (pintype "passive"))
    )
    (net (code "97") (name "DDR_CH1_DQ0_C") (class "Default")
      (node (ref "U3801") (pin "B2") (pinfunction "DQ0_a_B2") (pintype "passive"))
    )
    (net (code "98") (name "DDR_CH1_DQ0_D") (class "Default")
      (node (ref "U3801") (pin "AA2") (pinfunction "DQ0_b_AA2") (pintype "passive"))
    )
    (net (code "99") (name "DDR_CH1_DQ1_C") (class "Default")
      (node (ref "U3801") (pin "C2") (pinfunction "DQ1_a_C2") (pintype "passive"))
    )
    (net (code "100") (name "DDR_CH1_DQ1_D") (class "Default")
      (node (ref "U3801") (pin "Y2") (pinfunction "DQ1_b_Y2") (pintype "passive"))
    )
    (net (code "101") (name "DDR_CH1_DQ2_C") (class "Default")
      (node (ref "U3801") (pin "E2") (pinfunction "DQ2_a_E2") (pintype "passive"))
    )
    (net (code "102") (name "DDR_CH1_DQ2_D") (class "Default")
      (node (ref "U3801") (pin "V2") (pinfunction "DQ2_b_V2") (pintype "passive"))
    )
    (net (code "103") (name "DDR_CH1_DQ3_C") (class "Default")
      (node (ref "U3801") (pin "F2") (pinfunction "DQ3_a_F2") (pintype "passive"))
    )
    (net (code "104") (name "DDR_CH1_DQ3_D") (class "Default")
      (node (ref "U3801") (pin "U2") (pinfunction "DQ3_b_U2") (pintype "passive"))
    )
    (net (code "105") (name "DDR_CH1_DQ4_C") (class "Default")
      (node (ref "U3801") (pin "F4") (pinfunction "DQ4_a_F4") (pintype "passive"))
    )
    (net (code "106") (name "DDR_CH1_DQ4_D") (class "Default")
      (node (ref "U3801") (pin "U4") (pinfunction "DQ4_b_U4") (pintype "passive"))
    )
    (net (code "107") (name "DDR_CH1_DQ5_C") (class "Default")
      (node (ref "U3801") (pin "E4") (pinfunction "DQ5_a_E4") (pintype "passive"))
    )
    (net (code "108") (name "DDR_CH1_DQ5_D") (class "Default")
      (node (ref "U3801") (pin "V4") (pinfunction "DQ5_b_V4") (pintype "passive"))
    )
    (net (code "109") (name "DDR_CH1_DQ6_C") (class "Default")
      (node (ref "U3801") (pin "C4") (pinfunction "DQ6_a_C4") (pintype "passive"))
    )
    (net (code "110") (name "DDR_CH1_DQ6_D") (class "Default")
      (node (ref "U3801") (pin "Y4") (pinfunction "DQ6_b_Y4") (pintype "passive"))
    )
    (net (code "111") (name "DDR_CH1_DQ7_C") (class "Default")
      (node (ref "U3801") (pin "B4") (pinfunction "DQ7_a_B4") (pintype "passive"))
    )
    (net (code "112") (name "DDR_CH1_DQ7_D") (class "Default")
      (node (ref "U3801") (pin "AA4") (pinfunction "DQ7_b_AA4") (pintype "passive"))
    )
    (net (code "113") (name "DDR_CH1_DQ8_C") (class "Default")
      (node (ref "U3801") (pin "B11") (pinfunction "DQ8_a_B11") (pintype "passive"))
    )
    (net (code "114") (name "DDR_CH1_DQ8_D") (class "Default")
      (node (ref "U3801") (pin "AA11") (pinfunction "DQ8_b_AA11") (pintype "passive"))
    )
    (net (code "115") (name "DDR_CH1_DQ9_C") (class "Default")
      (node (ref "U3801") (pin "C11") (pinfunction "DQ9_a_C11") (pintype "passive"))
    )
    (net (code "116") (name "DDR_CH1_DQ9_D") (class "Default")
      (node (ref "U3801") (pin "Y11") (pinfunction "DQ9_b_Y11") (pintype "passive"))
    )
    (net (code "117") (name "DDR_CH1_DQ10_C") (class "Default")
      (node (ref "U3801") (pin "E11") (pinfunction "DQ10_a_E11") (pintype "passive"))
    )
    (net (code "118") (name "DDR_CH1_DQ10_D") (class "Default")
      (node (ref "U3801") (pin "V11") (pinfunction "DQ10_b_V11") (pintype "passive"))
    )
    (net (code "119") (name "DDR_CH1_DQ11_C") (class "Default")
      (node (ref "U3801") (pin "F11") (pinfunction "DQ11_a_F11") (pintype "passive"))
    )
    (net (code "120") (name "DDR_CH1_DQ11_D") (class "Default")
      (node (ref "U3801") (pin "U11") (pinfunction "DQ11_b_U11") (pintype "passive"))
    )
    (net (code "121") (name "DDR_CH1_DQ12_C") (class "Default")
      (node (ref "U3801") (pin "F9") (pinfunction "DQ12_a_F9") (pintype "passive"))
    )
    (net (code "122") (name "DDR_CH1_DQ12_D") (class "Default")
      (node (ref "U3801") (pin "U9") (pinfunction "DQ12_b_U9") (pintype "passive"))
    )
    (net (code "123") (name "DDR_CH1_DQ13_C") (class "Default")
      (node (ref "U3801") (pin "E9") (pinfunction "DQ13_a_E9") (pintype "passive"))
    )
    (net (code "124") (name "DDR_CH1_DQ13_D") (class "Default")
      (node (ref "U3801") (pin "V9") (pinfunction "DQ13_b_V9") (pintype "passive"))
    )
    (net (code "125") (name "DDR_CH1_DQ14_C") (class "Default")
      (node (ref "U3801") (pin "C9") (pinfunction "DQ14_a_C9") (pintype "passive"))
    )
    (net (code "126") (name "DDR_CH1_DQ14_D") (class "Default")
      (node (ref "U3801") (pin "Y9") (pinfunction "DQ14_b_Y9") (pintype "passive"))
    )
    (net (code "127") (name "DDR_CH1_DQ15_C") (class "Default")
      (node (ref "U3801") (pin "B9") (pinfunction "DQ15_a_B9") (pintype "passive"))
    )
    (net (code "128") (name "DDR_CH1_DQ15_D") (class "Default")
      (node (ref "U3801") (pin "AA9") (pinfunction "DQ15_b_AA9") (pintype "passive"))
    )
    (net (code "129") (name "DDR_CH1_DQS0N_C") (class "Default")
      (node (ref "U3801") (pin "E3") (pinfunction "DQS0_c_a_E3") (pintype "passive"))
    )
    (net (code "130") (name "DDR_CH1_DQS0N_D") (class "Default")
      (node (ref "U3801") (pin "V3") (pinfunction "DQS0_c_b_V3") (pintype "passive"))
    )
    (net (code "131") (name "DDR_CH1_DQS0P_C") (class "Default")
      (node (ref "U3801") (pin "D3") (pinfunction "DQS0_t_a_D3") (pintype "passive"))
    )
    (net (code "132") (name "DDR_CH1_DQS0P_D") (class "Default")
      (node (ref "U3801") (pin "W3") (pinfunction "DQS0_t_b_W3") (pintype "passive"))
    )
    (net (code "133") (name "DDR_CH1_DQS1N_C") (class "Default")
      (node (ref "U3801") (pin "E10") (pinfunction "DQS1_c_a_E10") (pintype "passive"))
    )
    (net (code "134") (name "DDR_CH1_DQS1N_D") (class "Default")
      (node (ref "U3801") (pin "V10") (pinfunction "DQS1_c_b_V10") (pintype "passive"))
    )
    (net (code "135") (name "DDR_CH1_DQS1P_C") (class "Default")
      (node (ref "U3801") (pin "D10") (pinfunction "DQS1_t_a_D10") (pintype "passive"))
    )
    (net (code "136") (name "DDR_CH1_DQS1P_D") (class "Default")
      (node (ref "U3801") (pin "W10") (pinfunction "DQS1_t_b_W10") (pintype "passive"))
    )
    (net (code "137") (name "DDR_CH1_LP4{slash}4X_CKE0{slash}LP5_CS0_C") (class "Default")
      (node (ref "R3812") (pin "1") (pinfunction "1_1") (pintype "passive"))
    )
    (net (code "138") (name "DDR_CH1_LP4{slash}4X_CKE0{slash}LP5_CS0_D") (class "Default")
      (node (ref "R3814") (pin "1") (pinfunction "1_1") (pintype "passive"))
    )
    (net (code "139") (name "DDR_CH1_LP4{slash}4X_CKE1{slash}LP5_CS1_C") (class "Default")
      (node (ref "R3813") (pin "1") (pinfunction "1_1") (pintype "passive"))
    )
    (net (code "140") (name "DDR_CH1_LP4{slash}4X_CKE1{slash}LP5_CS1_D") (class "Default")
      (node (ref "R3815") (pin "1") (pinfunction "1_1") (pintype "passive"))
    )
    (net (code "141") (name "DDR_CH1_LP4{slash}4X_CS0_C") (class "Default")
      (node (ref "U3801") (pin "H4") (pinfunction "CS0_a_H4") (pintype "passive"))
    )
    (net (code "142") (name "DDR_CH1_LP4{slash}4X_CS0_D") (class "Default")
      (node (ref "U3801") (pin "R4") (pinfunction "CS0_b_R4") (pintype "passive"))
    )
    (net (code "143") (name "DDR_CH1_LP4{slash}4X_CS1_C") (class "Default")
      (node (ref "U3801") (pin "H3") (pinfunction "CS1_a_H3") (pintype "passive"))
    )
    (net (code "144") (name "DDR_CH1_LP4{slash}4X_CS1_D") (class "Default")
      (node (ref "U3801") (pin "R3") (pinfunction "CS1_b_R3") (pintype "passive"))
    )
    (net (code "145") (name "DDR_RESET") (class "Default")
      (node (ref "C3844") (pin "1") (pinfunction "1_1") (pintype "passive"))
      (node (ref "C3888") (pin "1") (pinfunction "1_1") (pintype "passive"))
      (node (ref "U3800") (pin "T11") (pinfunction "RESET_n_T11") (pintype "passive"))
      (node (ref "U3801") (pin "T11") (pinfunction "RESET_n_T11") (pintype "passive"))
    )
    (net (code "146") (name "GND") (class "Default")
      (node (ref "C3800") (pin "2") (pinfunction "2_2") (pintype "passive"))
      (node (ref "C3801") (pin "2") (pinfunction "2_2") (pintype "passive"))
      (node (ref "C3802") (pin "2") (pinfunction "2_2") (pintype "passive"))
      (node (ref "C3803") (pin "2") (pinfunction "2_2") (pintype "passive"))
      (node (ref "C3804") (pin "2") (pinfunction "2_2") (pintype "passive"))
      (node (ref "C3805") (pin "2") (pinfunction "2_2") (pintype "passive"))
      (node (ref "C3806") (pin "2") (pinfunction "2_2") (pintype "passive"))
      (node (ref "C3807") (pin "2") (pinfunction "2_2") (pintype "passive"))
      (node (ref "C3808") (pin "2") (pinfunction "2_2") (pintype "passive"))
      (node (ref "C3809") (pin "2") (pinfunction "2_2") (pintype "passive"))
      (node (ref "C3810") (pin "2") (pinfunction "2_2") (pintype "passive"))
      (node (ref "C3811") (pin "2") (pinfunction "2_2") (pintype "passive"))
      (node (ref "C3812") (pin "2") (pinfunction "2_2") (pintype "passive"))
      (node (ref "C3813") (pin "2") (pinfunction "2_2") (pintype "passive"))
      (node (ref "C3814") (pin "2") (pinfunction "2_2") (pintype "passive"))
      (node (ref "C3815") (pin "2") (pinfunction "2_2") (pintype "passive"))
      (node (ref "C3816") (pin "2") (pinfunction "2_2") (pintype "passive"))
      (node (ref "C3817") (pin "2") (pinfunction "2_2") (pintype "passive"))
      (node (ref "C3818") (pin "2") (pinfunction "2_2") (pintype "passive"))
      (node (ref "C3819") (pin "2") (pinfunction "2_2") (pintype "passive"))
      (node (ref "C3820") (pin "2") (pinfunction "2_2") (pintype "passive"))
      (node (ref "C3821") (pin "2") (pinfunction "2_2") (pintype "passive"))
      (node (ref "C3822") (pin "2") (pinfunction "2_2") (pintype "passive"))
      (node (ref "C3823") (pin "2") (pinfunction "2_2") (pintype "passive"))
      (node (ref "C3824") (pin "2") (pinfunction "2_2") (pintype "passive"))
      (node (ref "C3825") (pin "2") (pinfunction "2_2") (pintype "passive"))
      (node (ref "C3826") (pin "2") (pinfunction "2_2") (pintype "passive"))
      (node (ref "C3827") (pin "2") (pinfunction "2_2") (pintype "passive"))
      (node (ref "C3828") (pin "2") (pinfunction "2_2") (pintype "passive"))
      (node (ref "C3829") (pin "2") (pinfunction "2_2") (pintype "passive"))
      (node (ref "C3830") (pin "2") (pinfunction "2_2") (pintype "passive"))
      (node (ref "C3831") (pin "2") (pinfunction "2_2") (pintype "passive"))
      (node (ref "C3832") (pin "2") (pinfunction "2_2") (pintype "passive"))
      (node (ref "C3833") (pin "2") (pinfunction "2_2") (pintype "passive"))
      (node (ref "C3834") (pin "2") (pinfunction "2_2") (pintype "passive"))
      (node (ref "C3835") (pin "2") (pinfunction "2_2") (pintype "passive"))
      (node (ref "C3836") (pin "2") (pinfunction "2_2") (pintype "passive"))
      (node (ref "C3837") (pin "2") (pinfunction "2_2") (pintype "passive"))
      (node (ref "C3838") (pin "2") (pinfunction "2_2") (pintype "passive"))
      (node (ref "C3839") (pin "2") (pinfunction "2_2") (pintype "passive"))
      (node (ref "C3840") (pin "2") (pinfunction "2_2") (pintype "passive"))
      (node (ref "C3841") (pin "2") (pinfunction "2_2") (pintype "passive"))
      (node (ref "C3842") (pin "2") (pinfunction "2_2") (pintype "passive"))
      (node (ref "C3843") (pin "2") (pinfunction "2_2") (pintype "passive"))
      (node (ref "C3844") (pin "2") (pinfunction "2_2") (pintype "passive"))
      (node (ref "C3845") (pin "2") (pinfunction "2_2") (pintype "passive"))
      (node (ref "C3846") (pin "2") (pinfunction "2_2") (pintype "passive"))
      (node (ref "C3847") (pin "2") (pinfunction "2_2") (pintype "passive"))
      (node (ref "C3848") (pin "2") (pinfunction "2_2") (pintype "passive"))
      (node (ref "C3849") (pin "2") (pinfunction "2_2") (pintype "passive"))
      (node (ref "C3850") (pin "2") (pinfunction "2_2") (pintype "passive"))
      (node (ref "C3851") (pin "2") (pinfunction "2_2") (pintype "passive"))
      (node (ref "C3852") (pin "2") (pinfunction "2_2") (pintype "passive"))
      (node (ref "C3853") (pin "2") (pinfunction "2_2") (pintype "passive"))
      (node (ref "C3854") (pin "2") (pinfunction "2_2") (pintype "passive"))
      (node (ref "C3855") (pin "2") (pinfunction "2_2") (pintype "passive"))
      (node (ref "C3856") (pin "2") (pinfunction "2_2") (pintype "passive"))
      (node (ref "C3857") (pin "2") (pinfunction "2_2") (pintype "passive"))
      (node (ref "C3858") (pin "2") (pinfunction "2_2") (pintype "passive"))
      (node (ref "C3859") (pin "2") (pinfunction "2_2") (pintype "passive"))
      (node (ref "C3860") (pin "2") (pinfunction "2_2") (pintype "passive"))
      (node (ref "C3861") (pin "2") (pinfunction "2_2") (pintype "passive"))
      (node (ref "C3862") (pin "2") (pinfunction "2_2") (pintype "passive"))
      (node (ref "C3863") (pin "2") (pinfunction "2_2") (pintype "passive"))
      (node (ref "C3864") (pin "2") (pinfunction "2_2") (pintype "passive"))
      (node (ref "C3865") (pin "2") (pinfunction "2_2") (pintype "passive"))
      (node (ref "C3866") (pin "2") (pinfunction "2_2") (pintype "passive"))
      (node (ref "C3867") (pin "2") (pinfunction "2_2") (pintype "passive"))
      (node (ref "C3868") (pin "2") (pinfunction "2_2") (pintype "passive"))
      (node (ref "C3869") (pin "2") (pinfunction "2_2") (pintype "passive"))
      (node (ref "C3870") (pin "2") (pinfunction "2_2") (pintype "passive"))
      (node (ref "C3871") (pin "2") (pinfunction "2_2") (pintype "passive"))
      (node (ref "C3872") (pin "2") (pinfunction "2_2") (pintype "passive"))
      (node (ref "C3873") (pin "2") (pinfunction "2_2") (pintype "passive"))
      (node (ref "C3874") (pin "2") (pinfunction "2_2") (pintype "passive"))
      (node (ref "C3875") (pin "2") (pinfunction "2_2") (pintype "passive"))
      (node (ref "C3876") (pin "2") (pinfunction "2_2") (pintype "passive"))
      (node (ref "C3877") (pin "2") (pinfunction "2_2") (pintype "passive"))
      (node (ref "C3878") (pin "2") (pinfunction "2_2") (pintype "passive"))
      (node (ref "C3879") (pin "2") (pinfunction "2_2") (pintype "passive"))
      (node (ref "C3880") (pin "2") (pinfunction "2_2") (pintype "passive"))
      (node (ref "C3881") (pin "2") (pinfunction "2_2") (pintype "passive"))
      (node (ref "C3882") (pin "2") (pinfunction "2_2") (pintype "passive"))
      (node (ref "C3883") (pin "2") (pinfunction "2_2") (pintype "passive"))
      (node (ref "C3884") (pin "2") (pinfunction "2_2") (pintype "passive"))
      (node (ref "C3885") (pin "2") (pinfunction "2_2") (pintype "passive"))
      (node (ref "C3886") (pin "2") (pinfunction "2_2") (pintype "passive"))
      (node (ref "C3887") (pin "2") (pinfunction "2_2") (pintype "passive"))
      (node (ref "C3888") (pin "2") (pinfunction "2_2") (pintype "passive"))
      (node (ref "U3800") (pin "A10") (pinfunction "VSS_2_A10") (pintype "power_in"))
      (node (ref "U3800") (pin "A3") (pinfunction "VSS_1_A3") (pintype "power_in"))
      (node (ref "U3800") (pin "AB10") (pinfunction "VSS_58_AB10") (pintype "power_in"))
      (node (ref "U3800") (pin "AB3") (pinfunction "VSS_55_AB3") (pintype "power_in"))
      (node (ref "U3800") (pin "AB5") (pinfunction "VSS_56_AB5") (pintype "power_in"))
      (node (ref "U3800") (pin "AB8") (pinfunction "VSS_57_AB8") (pintype "power_in"))
      (node (ref "U3800") (pin "C1") (pinfunction "VSS_3_C1") (pintype "power_in"))
      (node (ref "U3800") (pin "C12") (pinfunction "VSS_6_C12") (pintype "power_in"))
      (node (ref "U3800") (pin "C5") (pinfunction "VSS_4_C5") (pintype "power_in"))
      (node (ref "U3800") (pin "C8") (pinfunction "VSS_5_C8") (pintype "power_in"))
      (node (ref "U3800") (pin "D11") (pinfunction "VSS_10_D11") (pintype "power_in"))
      (node (ref "U3800") (pin "D2") (pinfunction "VSS_7_D2") (pintype "power_in"))
      (node (ref "U3800") (pin "D4") (pinfunction "VSS_8_D4") (pintype "power_in"))
      (node (ref "U3800") (pin "D9") (pinfunction "VSS_9_D9") (pintype "power_in"))
      (node (ref "U3800") (pin "E1") (pinfunction "VSS_11_E1") (pintype "power_in"))
      (node (ref "U3800") (pin "E12") (pinfunction "VSS_14_E12") (pintype "power_in"))
      (node (ref "U3800") (pin "E5") (pinfunction "VSS_12_E5") (pintype "power_in"))
      (node (ref "U3800") (pin "E8") (pinfunction "VSS_13_E8") (pintype "power_in"))
      (node (ref "U3800") (pin "G1") (pinfunction "VSS_15_G1") (pintype "power_in"))
      (node (ref "U3800") (pin "G10") (pinfunction "VSS_19_G10") (pintype "power_in"))
      (node (ref "U3800") (pin "G12") (pinfunction "VSS_20_G12") (pintype "power_in"))
      (node (ref "U3800") (pin "G3") (pinfunction "VSS_16_G3") (pintype "power_in"))
      (node (ref "U3800") (pin "G5") (pinfunction "VSS_17_G5") (pintype "power_in"))
      (node (ref "U3800") (pin "G8") (pinfunction "VSS_18_G8") (pintype "power_in"))
      (node (ref "U3800") (pin "J1") (pinfunction "VSS_21_J1") (pintype "power_in"))
      (node (ref "U3800") (pin "J10") (pinfunction "VSS_23_J10") (pintype "power_in"))
      (node (ref "U3800") (pin "J12") (pinfunction "VSS_24_J12") (pintype "power_in"))
      (node (ref "U3800") (pin "J3") (pinfunction "VSS_22_J3") (pintype "power_in"))
      (node (ref "U3800") (pin "K11") (pinfunction "VSS_28_K11") (pintype "power_in"))
      (node (ref "U3800") (pin "K2") (pinfunction "VSS_25_K2") (pintype "power_in"))
      (node (ref "U3800") (pin "K4") (pinfunction "VSS_26_K4") (pintype "power_in"))
      (node (ref "U3800") (pin "K9") (pinfunction "VSS_27_K9") (pintype "power_in"))
      (node (ref "U3800") (pin "N11") (pinfunction "VSS_32_N11") (pintype "power_in"))
      (node (ref "U3800") (pin "N2") (pinfunction "VSS_29_N2") (pintype "power_in"))
      (node (ref "U3800") (pin "N4") (pinfunction "VSS_30_N4") (pintype "power_in"))
      (node (ref "U3800") (pin "N9") (pinfunction "VSS_31_N9") (pintype "power_in"))
      (node (ref "U3800") (pin "P1") (pinfunction "VSS_33_P1") (pintype "power_in"))
      (node (ref "U3800") (pin "P10") (pinfunction "VSS_35_P10") (pintype "power_in"))
      (node (ref "U3800") (pin "P12") (pinfunction "VSS_36_P12") (pintype "power_in"))
      (node (ref "U3800") (pin "P3") (pinfunction "VSS_34_P3") (pintype "power_in"))
      (node (ref "U3800") (pin "T1") (pinfunction "VSS_37_T1") (pintype "power_in"))
      (node (ref "U3800") (pin "T10") (pinfunction "VSS_41_T10") (pintype "power_in"))
      (node (ref "U3800") (pin "T12") (pinfunction "VSS_42_T12") (pintype "power_in"))
      (node (ref "U3800") (pin "T3") (pinfunction "VSS_38_T3") (pintype "power_in"))
      (node (ref "U3800") (pin "T5") (pinfunction "VSS_39_T5") (pintype "power_in"))
      (node (ref "U3800") (pin "T8") (pinfunction "VSS_40_T8") (pintype "power_in"))
      (node (ref "U3800") (pin "V1") (pinfunction "VSS_43_V1") (pintype "power_in"))
      (node (ref "U3800") (pin "V12") (pinfunction "VSS_46_V12") (pintype "power_in"))
      (node (ref "U3800") (pin "V5") (pinfunction "VSS_44_V5") (pintype "power_in"))
      (node (ref "U3800") (pin "V8") (pinfunction "VSS_45_V8") (pintype "power_in"))
      (node (ref "U3800") (pin "W11") (pinfunction "VSS_50_W11") (pintype "power_in"))
      (node (ref "U3800") (pin "W2") (pinfunction "VSS_47_W2") (pintype "power_in"))
      (node (ref "U3800") (pin "W4") (pinfunction "VSS_48_W4") (pintype "power_in"))
      (node (ref "U3800") (pin "W9") (pinfunction "VSS_49_W9") (pintype "power_in"))
      (node (ref "U3800") (pin "Y1") (pinfunction "VSS_51_Y1") (pintype "power_in"))
      (node (ref "U3800") (pin "Y12") (pinfunction "VSS_54_Y12") (pintype "power_in"))
      (node (ref "U3800") (pin "Y5") (pinfunction "VSS_52_Y5") (pintype "power_in"))
      (node (ref "U3800") (pin "Y8") (pinfunction "VSS_53_Y8") (pintype "power_in"))
      (node (ref "U3801") (pin "A10") (pinfunction "VSS_2_A10") (pintype "power_in"))
      (node (ref "U3801") (pin "A3") (pinfunction "VSS_1_A3") (pintype "power_in"))
      (node (ref "U3801") (pin "AB10") (pinfunction "VSS_58_AB10") (pintype "power_in"))
      (node (ref "U3801") (pin "AB3") (pinfunction "VSS_55_AB3") (pintype "power_in"))
      (node (ref "U3801") (pin "AB5") (pinfunction "VSS_56_AB5") (pintype "power_in"))
      (node (ref "U3801") (pin "AB8") (pinfunction "VSS_57_AB8") (pintype "power_in"))
      (node (ref "U3801") (pin "C1") (pinfunction "VSS_3_C1") (pintype "power_in"))
      (node (ref "U3801") (pin "C12") (pinfunction "VSS_6_C12") (pintype "power_in"))
      (node (ref "U3801") (pin "C5") (pinfunction "VSS_4_C5") (pintype "power_in"))
      (node (ref "U3801") (pin "C8") (pinfunction "VSS_5_C8") (pintype "power_in"))
      (node (ref "U3801") (pin "D11") (pinfunction "VSS_10_D11") (pintype "power_in"))
      (node (ref "U3801") (pin "D2") (pinfunction "VSS_7_D2") (pintype "power_in"))
      (node (ref "U3801") (pin "D4") (pinfunction "VSS_8_D4") (pintype "power_in"))
      (node (ref "U3801") (pin "D9") (pinfunction "VSS_9_D9") (pintype "power_in"))
      (node (ref "U3801") (pin "E1") (pinfunction "VSS_11_E1") (pintype "power_in"))
      (node (ref "U3801") (pin "E12") (pinfunction "VSS_14_E12") (pintype "power_in"))
      (node (ref "U3801") (pin "E5") (pinfunction "VSS_12_E5") (pintype "power_in"))
      (node (ref "U3801") (pin "E8") (pinfunction "VSS_13_E8") (pintype "power_in"))
      (node (ref "U3801") (pin "G1") (pinfunction "VSS_15_G1") (pintype "power_in"))
      (node (ref "U3801") (pin "G10") (pinfunction "VSS_19_G10") (pintype "power_in"))
      (node (ref "U3801") (pin "G12") (pinfunction "VSS_20_G12") (pintype "power_in"))
      (node (ref "U3801") (pin "G3") (pinfunction "VSS_16_G3") (pintype "power_in"))
      (node (ref "U3801") (pin "G5") (pinfunction "VSS_17_G5") (pintype "power_in"))
      (node (ref "U3801") (pin "G8") (pinfunction "VSS_18_G8") (pintype "power_in"))
      (node (ref "U3801") (pin "J1") (pinfunction "VSS_21_J1") (pintype "power_in"))
      (node (ref "U3801") (pin "J10") (pinfunction "VSS_23_J10") (pintype "power_in"))
      (node (ref "U3801") (pin "J12") (pinfunction "VSS_24_J12") (pintype "power_in"))
      (node (ref "U3801") (pin "J3") (pinfunction "VSS_22_J3") (pintype "power_in"))
      (node (ref "U3801") (pin "K11") (pinfunction "VSS_28_K11") (pintype "power_in"))
      (node (ref "U3801") (pin "K2") (pinfunction "VSS_25_K2") (pintype "power_in"))
      (node (ref "U3801") (pin "K4") (pinfunction "VSS_26_K4") (pintype "power_in"))
      (node (ref "U3801") (pin "K9") (pinfunction "VSS_27_K9") (pintype "power_in"))
      (node (ref "U3801") (pin "N11") (pinfunction "VSS_32_N11") (pintype "power_in"))
      (node (ref "U3801") (pin "N2") (pinfunction "VSS_29_N2") (pintype "power_in"))
      (node (ref "U3801") (pin "N4") (pinfunction "VSS_30_N4") (pintype "power_in"))
      (node (ref "U3801") (pin "N9") (pinfunction "VSS_31_N9") (pintype "power_in"))
      (node (ref "U3801") (pin "P1") (pinfunction "VSS_33_P1") (pintype "power_in"))
      (node (ref "U3801") (pin "P10") (pinfunction "VSS_35_P10") (pintype "power_in"))
      (node (ref "U3801") (pin "P12") (pinfunction "VSS_36_P12") (pintype "power_in"))
      (node (ref "U3801") (pin "P3") (pinfunction "VSS_34_P3") (pintype "power_in"))
      (node (ref "U3801") (pin "T1") (pinfunction "VSS_37_T1") (pintype "power_in"))
      (node (ref "U3801") (pin "T10") (pinfunction "VSS_41_T10") (pintype "power_in"))
      (node (ref "U3801") (pin "T12") (pinfunction "VSS_42_T12") (pintype "power_in"))
      (node (ref "U3801") (pin "T3") (pinfunction "VSS_38_T3") (pintype "power_in"))
      (node (ref "U3801") (pin "T5") (pinfunction "VSS_39_T5") (pintype "power_in"))
      (node (ref "U3801") (pin "T8") (pinfunction "VSS_40_T8") (pintype "power_in"))
      (node (ref "U3801") (pin "V1") (pinfunction "VSS_43_V1") (pintype "power_in"))
      (node (ref "U3801") (pin "V12") (pinfunction "VSS_46_V12") (pintype "power_in"))
      (node (ref "U3801") (pin "V5") (pinfunction "VSS_44_V5") (pintype "power_in"))
      (node (ref "U3801") (pin "V8") (pinfunction "VSS_45_V8") (pintype "power_in"))
      (node (ref "U3801") (pin "W11") (pinfunction "VSS_50_W11") (pintype "power_in"))
      (node (ref "U3801") (pin "W2") (pinfunction "VSS_47_W2") (pintype "power_in"))
      (node (ref "U3801") (pin "W4") (pinfunction "VSS_48_W4") (pintype "power_in"))
      (node (ref "U3801") (pin "W9") (pinfunction "VSS_49_W9") (pintype "power_in"))
      (node (ref "U3801") (pin "Y1") (pinfunction "VSS_51_Y1") (pintype "power_in"))
      (node (ref "U3801") (pin "Y12") (pinfunction "VSS_54_Y12") (pintype "power_in"))
      (node (ref "U3801") (pin "Y5") (pinfunction "VSS_52_Y5") (pintype "power_in"))
      (node (ref "U3801") (pin "Y8") (pinfunction "VSS_53_Y8") (pintype "power_in"))
    )
    (net (code "147") (name "Net-(U3800A-ODT_CA_a)") (class "Default")
      (node (ref "R3806") (pin "2") (pinfunction "2_2") (pintype "passive"))
      (node (ref "U3800") (pin "G2") (pinfunction "ODT_CA_a_G2") (pintype "passive"))
    )
    (net (code "148") (name "Net-(U3800A-ODT_CA_b)") (class "Default")
      (node (ref "R3807") (pin "1") (pinfunction "1_1") (pintype "passive"))
      (node (ref "U3800") (pin "T2") (pinfunction "ODT_CA_b_T2") (pintype "passive"))
    )
    (net (code "149") (name "Net-(U3800A-ZQ0)") (class "Default")
      (node (ref "R3809") (pin "2") (pinfunction "2_2") (pintype "passive"))
      (node (ref "U3800") (pin "A5") (pinfunction "ZQ0_A5") (pintype "passive"))
    )
    (net (code "150") (name "Net-(U3800A-ZQ1)") (class "Default")
      (node (ref "R3810") (pin "2") (pinfunction "2_2") (pintype "passive"))
      (node (ref "U3800") (pin "A8") (pinfunction "ZQ1_A8") (pintype "passive"))
    )
    (net (code "151") (name "Net-(U3801A-ODT_CA_a)") (class "Default")
      (node (ref "R3816") (pin "2") (pinfunction "2_2") (pintype "passive"))
      (node (ref "U3801") (pin "G2") (pinfunction "ODT_CA_a_G2") (pintype "passive"))
    )
    (net (code "152") (name "Net-(U3801A-ODT_CA_b)") (class "Default")
      (node (ref "R3817") (pin "1") (pinfunction "1_1") (pintype "passive"))
      (node (ref "U3801") (pin "T2") (pinfunction "ODT_CA_b_T2") (pintype "passive"))
    )
    (net (code "153") (name "Net-(U3801A-ZQ0)") (class "Default")
      (node (ref "R3818") (pin "2") (pinfunction "2_2") (pintype "passive"))
      (node (ref "U3801") (pin "A5") (pinfunction "ZQ0_A5") (pintype "passive"))
    )
    (net (code "154") (name "Net-(U3801A-ZQ1)") (class "Default")
      (node (ref "R3819") (pin "2") (pinfunction "2_2") (pintype "passive"))
      (node (ref "U3801") (pin "A8") (pinfunction "ZQ1_A8") (pintype "passive"))
    )
    (net (code "155") (name "VCCA1V8_PLDO6") (class "Default")
      (node (ref "R3800") (pin "2") (pinfunction "2_2") (pintype "passive"))
    )
    (net (code "156") (name "VCC_1V8") (class "Default")
      (node (ref "C3843") (pin "1") (pinfunction "1_1") (pintype "passive"))
      (node (ref "R3803") (pin "2") (pinfunction "2_2") (pintype "passive"))
    )
    (net (code "157") (name "VDD1_1V8_DDR") (class "Default")
      (node (ref "C3800") (pin "1") (pinfunction "1_1") (pintype "passive"))
      (node (ref "C3801") (pin "1") (pinfunction "1_1") (pintype "passive"))
      (node (ref "C3802") (pin "1") (pinfunction "1_1") (pintype "passive"))
      (node (ref "C3803") (pin "1") (pinfunction "1_1") (pintype "passive"))
      (node (ref "C3804") (pin "1") (pinfunction "1_1") (pintype "passive"))
      (node (ref "C3805") (pin "1") (pinfunction "1_1") (pintype "passive"))
      (node (ref "C3806") (pin "1") (pinfunction "1_1") (pintype "passive"))
      (node (ref "C3807") (pin "1") (pinfunction "1_1") (pintype "passive"))
      (node (ref "C3808") (pin "1") (pinfunction "1_1") (pintype "passive"))
      (node (ref "C3845") (pin "1") (pinfunction "1_1") (pintype "passive"))
      (node (ref "C3846") (pin "1") (pinfunction "1_1") (pintype "passive"))
      (node (ref "C3847") (pin "1") (pinfunction "1_1") (pintype "passive"))
      (node (ref "C3848") (pin "1") (pinfunction "1_1") (pintype "passive"))
      (node (ref "C3849") (pin "1") (pinfunction "1_1") (pintype "passive"))
      (node (ref "C3850") (pin "1") (pinfunction "1_1") (pintype "passive"))
      (node (ref "C3851") (pin "1") (pinfunction "1_1") (pintype "passive"))
      (node (ref "C3852") (pin "1") (pinfunction "1_1") (pintype "passive"))
      (node (ref "C3853") (pin "1") (pinfunction "1_1") (pintype "passive"))
      (node (ref "R3800") (pin "1") (pinfunction "1_1") (pintype "passive"))
      (node (ref "R3803") (pin "1") (pinfunction "1_1") (pintype "passive"))
      (node (ref "U3800") (pin "F1") (pinfunction "VDD1_1_F1") (pintype "power_in"))
      (node (ref "U3800") (pin "F12") (pinfunction "VDD1_2_F12") (pintype "power_in"))
      (node (ref "U3800") (pin "G4") (pinfunction "VDD1_3_G4") (pintype "power_in"))
      (node (ref "U3800") (pin "G9") (pinfunction "VDD1_4_G9") (pintype "power_in"))
      (node (ref "U3800") (pin "T4") (pinfunction "VDD1_5_T4") (pintype "power_in"))
      (node (ref "U3800") (pin "T9") (pinfunction "VDD1_6_T9") (pintype "power_in"))
      (node (ref "U3800") (pin "U1") (pinfunction "VDD1_7_U1") (pintype "power_in"))
      (node (ref "U3800") (pin "U12") (pinfunction "VDD1_8_U12") (pintype "power_in"))
      (node (ref "U3801") (pin "F1") (pinfunction "VDD1_1_F1") (pintype "power_in"))
      (node (ref "U3801") (pin "F12") (pinfunction "VDD1_2_F12") (pintype "power_in"))
      (node (ref "U3801") (pin "G4") (pinfunction "VDD1_3_G4") (pintype "power_in"))
      (node (ref "U3801") (pin "G9") (pinfunction "VDD1_4_G9") (pintype "power_in"))
      (node (ref "U3801") (pin "T4") (pinfunction "VDD1_5_T4") (pintype "power_in"))
      (node (ref "U3801") (pin "T9") (pinfunction "VDD1_6_T9") (pintype "power_in"))
      (node (ref "U3801") (pin "U1") (pinfunction "VDD1_7_U1") (pintype "power_in"))
      (node (ref "U3801") (pin "U12") (pinfunction "VDD1_8_U12") (pintype "power_in"))
    )
    (net (code "158") (name "VDD2_DDR") (class "Default")
      (node (ref "C3809") (pin "1") (pinfunction "1_1") (pintype "passive"))
      (node (ref "C3810") (pin "1") (pinfunction "1_1") (pintype "passive"))
      (node (ref "C3811") (pin "1") (pinfunction "1_1") (pintype "passive"))
      (node (ref "C3812") (pin "1") (pinfunction "1_1") (pintype "passive"))
      (node (ref "C3813") (pin "1") (pinfunction "1_1") (pintype "passive"))
      (node (ref "C3814") (pin "1") (pinfunction "1_1") (pintype "passive"))
      (node (ref "C3815") (pin "1") (pinfunction "1_1") (pintype "passive"))
      (node (ref "C3816") (pin "1") (pinfunction "1_1") (pintype "passive"))
      (node (ref "C3817") (pin "1") (pinfunction "1_1") (pintype "passive"))
      (node (ref "C3818") (pin "1") (pinfunction "1_1") (pintype "passive"))
      (node (ref "C3819") (pin "1") (pinfunction "1_1") (pintype "passive"))
      (node (ref "C3820") (pin "1") (pinfunction "1_1") (pintype "passive"))
      (node (ref "C3821") (pin "1") (pinfunction "1_1") (pintype "passive"))
      (node (ref "C3822") (pin "1") (pinfunction "1_1") (pintype "passive"))
      (node (ref "C3823") (pin "1") (pinfunction "1_1") (pintype "passive"))
      (node (ref "C3854") (pin "1") (pinfunction "1_1") (pintype "passive"))
      (node (ref "C3855") (pin "1") (pinfunction "1_1") (pintype "passive"))
      (node (ref "C3856") (pin "1") (pinfunction "1_1") (pintype "passive"))
      (node (ref "C3857") (pin "1") (pinfunction "1_1") (pintype "passive"))
      (node (ref "C3858") (pin "1") (pinfunction "1_1") (pintype "passive"))
      (node (ref "C3859") (pin "1") (pinfunction "1_1") (pintype "passive"))
      (node (ref "C3860") (pin "1") (pinfunction "1_1") (pintype "passive"))
      (node (ref "C3861") (pin "1") (pinfunction "1_1") (pintype "passive"))
      (node (ref "C3862") (pin "1") (pinfunction "1_1") (pintype "passive"))
      (node (ref "C3863") (pin "1") (pinfunction "1_1") (pintype "passive"))
      (node (ref "C3864") (pin "1") (pinfunction "1_1") (pintype "passive"))
      (node (ref "C3865") (pin "1") (pinfunction "1_1") (pintype "passive"))
      (node (ref "C3866") (pin "1") (pinfunction "1_1") (pintype "passive"))
      (node (ref "C3867") (pin "1") (pinfunction "1_1") (pintype "passive"))
      (node (ref "C3868") (pin "1") (pinfunction "1_1") (pintype "passive"))
      (node (ref "R3806") (pin "1") (pinfunction "1_1") (pintype "passive"))
      (node (ref "R3807") (pin "2") (pinfunction "2_2") (pintype "passive"))
      (node (ref "R3811") (pin "2") (pinfunction "2_2") (pintype "passive"))
      (node (ref "R3816") (pin "1") (pinfunction "1_1") (pintype "passive"))
      (node (ref "R3817") (pin "2") (pinfunction "2_2") (pintype "passive"))
      (node (ref "U3800") (pin "A4") (pinfunction "VDD2_1_A4") (pintype "power_in"))
      (node (ref "U3800") (pin "A9") (pinfunction "VDD2_2_A9") (pintype "power_in"))
      (node (ref "U3800") (pin "AB4") (pinfunction "VDD2_23_AB4") (pintype "power_in"))
      (node (ref "U3800") (pin "AB9") (pinfunction "VDD2_24_AB9") (pintype "power_in"))
      (node (ref "U3800") (pin "F5") (pinfunction "VDD2_3_F5") (pintype "power_in"))
      (node (ref "U3800") (pin "F8") (pinfunction "VDD2_4_F8") (pintype "power_in"))
      (node (ref "U3800") (pin "H1") (pinfunction "VDD2_5_H1") (pintype "power_in"))
      (node (ref "U3800") (pin "H12") (pinfunction "VDD2_8_H12") (pintype "power_in"))
      (node (ref "U3800") (pin "H5") (pinfunction "VDD2_6_H5") (pintype "power_in"))
      (node (ref "U3800") (pin "H8") (pinfunction "VDD2_7_H8") (pintype "power_in"))
      (node (ref "U3800") (pin "K1") (pinfunction "VDD2_9_K1") (pintype "power_in"))
      (node (ref "U3800") (pin "K10") (pinfunction "VDD2_11_K10") (pintype "power_in"))
      (node (ref "U3800") (pin "K12") (pinfunction "VDD2_12_K12") (pintype "power_in"))
      (node (ref "U3800") (pin "K3") (pinfunction "VDD2_10_K3") (pintype "power_in"))
      (node (ref "U3800") (pin "N1") (pinfunction "VDD2_13_N1") (pintype "power_in"))
      (node (ref "U3800") (pin "N10") (pinfunction "VDD2_15_N10") (pintype "power_in"))
      (node (ref "U3800") (pin "N12") (pinfunction "VDD2_16_N12") (pintype "power_in"))
      (node (ref "U3800") (pin "N3") (pinfunction "VDD2_14_N3") (pintype "power_in"))
      (node (ref "U3800") (pin "R1") (pinfunction "VDD2_17_R1") (pintype "power_in"))
      (node (ref "U3800") (pin "R12") (pinfunction "VDD2_20_R12") (pintype "power_in"))
      (node (ref "U3800") (pin "R5") (pinfunction "VDD2_18_R5") (pintype "power_in"))
      (node (ref "U3800") (pin "R8") (pinfunction "VDD2_19_R8") (pintype "power_in"))
      (node (ref "U3800") (pin "U5") (pinfunction "VDD2_21_U5") (pintype "power_in"))
      (node (ref "U3800") (pin "U8") (pinfunction "VDD2_22_U8") (pintype "power_in"))
      (node (ref "U3801") (pin "A4") (pinfunction "VDD2_1_A4") (pintype "power_in"))
      (node (ref "U3801") (pin "A9") (pinfunction "VDD2_2_A9") (pintype "power_in"))
      (node (ref "U3801") (pin "AB4") (pinfunction "VDD2_23_AB4") (pintype "power_in"))
      (node (ref "U3801") (pin "AB9") (pinfunction "VDD2_24_AB9") (pintype "power_in"))
      (node (ref "U3801") (pin "F5") (pinfunction "VDD2_3_F5") (pintype "power_in"))
      (node (ref "U3801") (pin "F8") (pinfunction "VDD2_4_F8") (pintype "power_in"))
      (node (ref "U3801") (pin "H1") (pinfunction "VDD2_5_H1") (pintype "power_in"))
      (node (ref "U3801") (pin "H12") (pinfunction "VDD2_8_H12") (pintype "power_in"))
      (node (ref "U3801") (pin "H5") (pinfunction "VDD2_6_H5") (pintype "power_in"))
      (node (ref "U3801") (pin "H8") (pinfunction "VDD2_7_H8") (pintype "power_in"))
      (node (ref "U3801") (pin "K1") (pinfunction "VDD2_9_K1") (pintype "power_in"))
      (node (ref "U3801") (pin "K10") (pinfunction "VDD2_11_K10") (pintype "power_in"))
      (node (ref "U3801") (pin "K12") (pinfunction "VDD2_12_K12") (pintype "power_in"))
      (node (ref "U3801") (pin "K3") (pinfunction "VDD2_10_K3") (pintype "power_in"))
      (node (ref "U3801") (pin "N1") (pinfunction "VDD2_13_N1") (pintype "power_in"))
      (node (ref "U3801") (pin "N10") (pinfunction "VDD2_15_N10") (pintype "power_in"))
      (node (ref "U3801") (pin "N12") (pinfunction "VDD2_16_N12") (pintype "power_in"))
      (node (ref "U3801") (pin "N3") (pinfunction "VDD2_14_N3") (pintype "power_in"))
      (node (ref "U3801") (pin "R1") (pinfunction "VDD2_17_R1") (pintype "power_in"))
      (node (ref "U3801") (pin "R12") (pinfunction "VDD2_20_R12") (pintype "power_in"))
      (node (ref "U3801") (pin "R5") (pinfunction "VDD2_18_R5") (pintype "power_in"))
      (node (ref "U3801") (pin "R8") (pinfunction "VDD2_19_R8") (pintype "power_in"))
      (node (ref "U3801") (pin "U5") (pinfunction "VDD2_21_U5") (pintype "power_in"))
      (node (ref "U3801") (pin "U8") (pinfunction "VDD2_22_U8") (pintype "power_in"))
    )
    (net (code "159") (name "VDDQ_DDR") (class "Default")
      (node (ref "R3808") (pin "2") (pinfunction "2_2") (pintype "passive"))
    )
    (net (code "160") (name "VDDQ_DRAM") (class "Default")
      (node (ref "C3824") (pin "1") (pinfunction "1_1") (pintype "passive"))
      (node (ref "C3825") (pin "1") (pinfunction "1_1") (pintype "passive"))
      (node (ref "C3826") (pin "1") (pinfunction "1_1") (pintype "passive"))
      (node (ref "C3827") (pin "1") (pinfunction "1_1") (pintype "passive"))
      (node (ref "C3828") (pin "1") (pinfunction "1_1") (pintype "passive"))
      (node (ref "C3829") (pin "1") (pinfunction "1_1") (pintype "passive"))
      (node (ref "C3830") (pin "1") (pinfunction "1_1") (pintype "passive"))
      (node (ref "C3831") (pin "1") (pinfunction "1_1") (pintype "passive"))
      (node (ref "C3832") (pin "1") (pinfunction "1_1") (pintype "passive"))
      (node (ref "C3833") (pin "1") (pinfunction "1_1") (pintype "passive"))
      (node (ref "C3834") (pin "1") (pinfunction "1_1") (pintype "passive"))
      (node (ref "C3835") (pin "1") (pinfunction "1_1") (pintype "passive"))
      (node (ref "C3836") (pin "1") (pinfunction "1_1") (pintype "passive"))
      (node (ref "C3837") (pin "1") (pinfunction "1_1") (pintype "passive"))
      (node (ref "C3838") (pin "1") (pinfunction "1_1") (pintype "passive"))
      (node (ref "C3839") (pin "1") (pinfunction "1_1") (pintype "passive"))
      (node (ref "C3840") (pin "1") (pinfunction "1_1") (pintype "passive"))
      (node (ref "C3841") (pin "1") (pinfunction "1_1") (pintype "passive"))
      (node (ref "C3842") (pin "1") (pinfunction "1_1") (pintype "passive"))
      (node (ref "C3869") (pin "1") (pinfunction "1_1") (pintype "passive"))
      (node (ref "C3870") (pin "1") (pinfunction "1_1") (pintype "passive"))
      (node (ref "C3871") (pin "1") (pinfunction "1_1") (pintype "passive"))
      (node (ref "C3872") (pin "1") (pinfunction "1_1") (pintype "passive"))
      (node (ref "C3873") (pin "1") (pinfunction "1_1") (pintype "passive"))
      (node (ref "C3874") (pin "1") (pinfunction "1_1") (pintype "passive"))
      (node (ref "C3875") (pin "1") (pinfunction "1_1") (pintype "passive"))
      (node (ref "C3876") (pin "1") (pinfunction "1_1") (pintype "passive"))
      (node (ref "C3877") (pin "1") (pinfunction "1_1") (pintype "passive"))
      (node (ref "C3878") (pin "1") (pinfunction "1_1") (pintype "passive"))
      (node (ref "C3879") (pin "1") (pinfunction "1_1") (pintype "passive"))
      (node (ref "C3880") (pin "1") (pinfunction "1_1") (pintype "passive"))
      (node (ref "C3881") (pin "1") (pinfunction "1_1") (pintype "passive"))
      (node (ref "C3882") (pin "1") (pinfunction "1_1") (pintype "passive"))
      (node (ref "C3883") (pin "1") (pinfunction "1_1") (pintype "passive"))
      (node (ref "C3884") (pin "1") (pinfunction "1_1") (pintype "passive"))
      (node (ref "C3885") (pin "1") (pinfunction "1_1") (pintype "passive"))
      (node (ref "C3886") (pin "1") (pinfunction "1_1") (pintype "passive"))
      (node (ref "C3887") (pin "1") (pinfunction "1_1") (pintype "passive"))
      (node (ref "R3808") (pin "1") (pinfunction "1_1") (pintype "passive"))
      (node (ref "R3809") (pin "1") (pinfunction "1_1") (pintype "passive"))
      (node (ref "R3810") (pin "1") (pinfunction "1_1") (pintype "passive"))
      (node (ref "R3811") (pin "1") (pinfunction "1_1") (pintype "passive"))
      (node (ref "R3818") (pin "1") (pinfunction "1_1") (pintype "passive"))
      (node (ref "R3819") (pin "1") (pinfunction "1_1") (pintype "passive"))
      (node (ref "U3800") (pin "AA10") (pinfunction "VDDQ_20_AA10") (pintype "power_in"))
      (node (ref "U3800") (pin "AA3") (pinfunction "VDDQ_17_AA3") (pintype "power_in"))
      (node (ref "U3800") (pin "AA5") (pinfunction "VDDQ_18_AA5") (pintype "power_in"))
      (node (ref "U3800") (pin "AA8") (pinfunction "VDDQ_19_AA8") (pintype "power_in"))
      (node (ref "U3800") (pin "B10") (pinfunction "VDDQ_4_B10") (pintype "power_in"))
      (node (ref "U3800") (pin "B3") (pinfunction "VDDQ_1_B3") (pintype "power_in"))
      (node (ref "U3800") (pin "B5") (pinfunction "VDDQ_2_B5") (pintype "power_in"))
      (node (ref "U3800") (pin "B8") (pinfunction "VDDQ_3_B8") (pintype "power_in"))
      (node (ref "U3800") (pin "D1") (pinfunction "VDDQ_5_D1") (pintype "power_in"))
      (node (ref "U3800") (pin "D12") (pinfunction "VDDQ_8_D12") (pintype "power_in"))
      (node (ref "U3800") (pin "D5") (pinfunction "VDDQ_6_D5") (pintype "power_in"))
      (node (ref "U3800") (pin "D8") (pinfunction "VDDQ_7_D8") (pintype "power_in"))
      (node (ref "U3800") (pin "F10") (pinfunction "VDDQ_10_F10") (pintype "power_in"))
      (node (ref "U3800") (pin "F3") (pinfunction "VDDQ_9_F3") (pintype "power_in"))
      (node (ref "U3800") (pin "U10") (pinfunction "VDDQ_12_U10") (pintype "power_in"))
      (node (ref "U3800") (pin "U3") (pinfunction "VDDQ_11_U3") (pintype "power_in"))
      (node (ref "U3800") (pin "W1") (pinfunction "VDDQ_13_W1") (pintype "power_in"))
      (node (ref "U3800") (pin "W12") (pinfunction "VDDQ_16_W12") (pintype "power_in"))
      (node (ref "U3800") (pin "W5") (pinfunction "VDDQ_14_W5") (pintype "power_in"))
      (node (ref "U3800") (pin "W8") (pinfunction "VDDQ_15_W8") (pintype "power_in"))
      (node (ref "U3801") (pin "AA10") (pinfunction "VDDQ_20_AA10") (pintype "power_in"))
      (node (ref "U3801") (pin "AA3") (pinfunction "VDDQ_17_AA3") (pintype "power_in"))
      (node (ref "U3801") (pin "AA5") (pinfunction "VDDQ_18_AA5") (pintype "power_in"))
      (node (ref "U3801") (pin "AA8") (pinfunction "VDDQ_19_AA8") (pintype "power_in"))
      (node (ref "U3801") (pin "B10") (pinfunction "VDDQ_4_B10") (pintype "power_in"))
      (node (ref "U3801") (pin "B3") (pinfunction "VDDQ_1_B3") (pintype "power_in"))
      (node (ref "U3801") (pin "B5") (pinfunction "VDDQ_2_B5") (pintype "power_in"))
      (node (ref "U3801") (pin "B8") (pinfunction "VDDQ_3_B8") (pintype "power_in"))
      (node (ref "U3801") (pin "D1") (pinfunction "VDDQ_5_D1") (pintype "power_in"))
      (node (ref "U3801") (pin "D12") (pinfunction "VDDQ_8_D12") (pintype "power_in"))
      (node (ref "U3801") (pin "D5") (pinfunction "VDDQ_6_D5") (pintype "power_in"))
      (node (ref "U3801") (pin "D8") (pinfunction "VDDQ_7_D8") (pintype "power_in"))
      (node (ref "U3801") (pin "F10") (pinfunction "VDDQ_10_F10") (pintype "power_in"))
      (node (ref "U3801") (pin "F3") (pinfunction "VDDQ_9_F3") (pintype "power_in"))
      (node (ref "U3801") (pin "U10") (pinfunction "VDDQ_12_U10") (pintype "power_in"))
      (node (ref "U3801") (pin "U3") (pinfunction "VDDQ_11_U3") (pintype "power_in"))
      (node (ref "U3801") (pin "W1") (pinfunction "VDDQ_13_W1") (pintype "power_in"))
      (node (ref "U3801") (pin "W12") (pinfunction "VDDQ_16_W12") (pintype "power_in"))
      (node (ref "U3801") (pin "W5") (pinfunction "VDDQ_14_W5") (pintype "power_in"))
      (node (ref "U3801") (pin "W8") (pinfunction "VDDQ_15_W8") (pintype "power_in"))
    )
    (net (code "161") (name "unconnected-(U3800A-CKE2_a_NC-PadK8)") (class "Default")
      (node (ref "U3800") (pin "K8") (pinfunction "CKE2_a_NC_K8") (pintype "passive+no_connect"))
    )
    (net (code "162") (name "unconnected-(U3800A-CKE2_b_NC-PadN8)") (class "Default")
      (node (ref "U3800") (pin "N8") (pinfunction "CKE2_b_NC_N8") (pintype "passive+no_connect"))
    )
    (net (code "163") (name "unconnected-(U3800A-CS2_a_NC-PadK5)") (class "Default")
      (node (ref "U3800") (pin "K5") (pinfunction "CS2_a_NC_K5") (pintype "passive+no_connect"))
    )
    (net (code "164") (name "unconnected-(U3800A-CS2_b_NC-PadN5)") (class "Default")
      (node (ref "U3800") (pin "N5") (pinfunction "CS2_b_NC_N5") (pintype "passive+no_connect"))
    )
    (net (code "165") (name "unconnected-(U3800A-ZQ2_NC-PadG11)") (class "Default")
      (node (ref "U3800") (pin "G11") (pinfunction "ZQ2_NC_G11") (pintype "passive+no_connect"))
    )
    (net (code "166") (name "unconnected-(U3800B-DNU_1-PadA1)") (class "Default")
      (node (ref "U3800") (pin "A1") (pinfunction "DNU_1_A1") (pintype "passive+no_connect"))
    )
    (net (code "167") (name "unconnected-(U3800B-DNU_2-PadA2)") (class "Default")
      (node (ref "U3800") (pin "A2") (pinfunction "DNU_2_A2") (pintype "passive+no_connect"))
    )
    (net (code "168") (name "unconnected-(U3800B-DNU_3-PadA11)") (class "Default")
      (node (ref "U3800") (pin "A11") (pinfunction "DNU_3_A11") (pintype "passive+no_connect"))
    )
    (net (code "169") (name "unconnected-(U3800B-DNU_4-PadA12)") (class "Default")
      (node (ref "U3800") (pin "A12") (pinfunction "DNU_4_A12") (pintype "passive+no_connect"))
    )
    (net (code "170") (name "unconnected-(U3800B-DNU_5-PadB1)") (class "Default")
      (node (ref "U3800") (pin "B1") (pinfunction "DNU_5_B1") (pintype "passive+no_connect"))
    )
    (net (code "171") (name "unconnected-(U3800B-DNU_6-PadB12)") (class "Default")
      (node (ref "U3800") (pin "B12") (pinfunction "DNU_6_B12") (pintype "passive+no_connect"))
    )
    (net (code "172") (name "unconnected-(U3800B-DNU_7-PadAA1)") (class "Default")
      (node (ref "U3800") (pin "AA1") (pinfunction "DNU_7_AA1") (pintype "passive+no_connect"))
    )
    (net (code "173") (name "unconnected-(U3800B-DNU_8-PadAA12)") (class "Default")
      (node (ref "U3800") (pin "AA12") (pinfunction "DNU_8_AA12") (pintype "passive+no_connect"))
    )
    (net (code "174") (name "unconnected-(U3800B-DNU_9-PadAB1)") (class "Default")
      (node (ref "U3800") (pin "AB1") (pinfunction "DNU_9_AB1") (pintype "passive+no_connect"))
    )
    (net (code "175") (name "unconnected-(U3800B-DNU_10-PadAB2)") (class "Default")
      (node (ref "U3800") (pin "AB2") (pinfunction "DNU_10_AB2") (pintype "passive+no_connect"))
    )
    (net (code "176") (name "unconnected-(U3800B-DNU_11-PadAB11)") (class "Default")
      (node (ref "U3800") (pin "AB11") (pinfunction "DNU_11_AB11") (pintype "passive+no_connect"))
    )
    (net (code "177") (name "unconnected-(U3800B-DNU_12-PadAB12)") (class "Default")
      (node (ref "U3800") (pin "AB12") (pinfunction "DNU_12_AB12") (pintype "passive+no_connect"))
    )
    (net (code "178") (name "unconnected-(U3801A-CKE2_a_NC-PadK8)") (class "Default")
      (node (ref "U3801") (pin "K8") (pinfunction "CKE2_a_NC_K8") (pintype "passive+no_connect"))
    )
    (net (code "179") (name "unconnected-(U3801A-CKE2_b_NC-PadN8)") (class "Default")
      (node (ref "U3801") (pin "N8") (pinfunction "CKE2_b_NC_N8") (pintype "passive+no_connect"))
    )
    (net (code "180") (name "unconnected-(U3801A-CS2_a_NC-PadK5)") (class "Default")
      (node (ref "U3801") (pin "K5") (pinfunction "CS2_a_NC_K5") (pintype "passive+no_connect"))
    )
    (net (code "181") (name "unconnected-(U3801A-CS2_b_NC-PadN5)") (class "Default")
      (node (ref "U3801") (pin "N5") (pinfunction "CS2_b_NC_N5") (pintype "passive+no_connect"))
    )
    (net (code "182") (name "unconnected-(U3801A-ZQ2_NC-PadG11)") (class "Default")
      (node (ref "U3801") (pin "G11") (pinfunction "ZQ2_NC_G11") (pintype "passive+no_connect"))
    )
    (net (code "183") (name "unconnected-(U3801B-DNU_1-PadA1)") (class "Default")
      (node (ref "U3801") (pin "A1") (pinfunction "DNU_1_A1") (pintype "passive+no_connect"))
    )
    (net (code "184") (name "unconnected-(U3801B-DNU_2-PadA2)") (class "Default")
      (node (ref "U3801") (pin "A2") (pinfunction "DNU_2_A2") (pintype "passive+no_connect"))
    )
    (net (code "185") (name "unconnected-(U3801B-DNU_3-PadA11)") (class "Default")
      (node (ref "U3801") (pin "A11") (pinfunction "DNU_3_A11") (pintype "passive+no_connect"))
    )
    (net (code "186") (name "unconnected-(U3801B-DNU_4-PadA12)") (class "Default")
      (node (ref "U3801") (pin "A12") (pinfunction "DNU_4_A12") (pintype "passive+no_connect"))
    )
    (net (code "187") (name "unconnected-(U3801B-DNU_5-PadB1)") (class "Default")
      (node (ref "U3801") (pin "B1") (pinfunction "DNU_5_B1") (pintype "passive+no_connect"))
    )
    (net (code "188") (name "unconnected-(U3801B-DNU_6-PadB12)") (class "Default")
      (node (ref "U3801") (pin "B12") (pinfunction "DNU_6_B12") (pintype "passive+no_connect"))
    )
    (net (code "189") (name "unconnected-(U3801B-DNU_7-PadAA1)") (class "Default")
      (node (ref "U3801") (pin "AA1") (pinfunction "DNU_7_AA1") (pintype "passive+no_connect"))
    )
    (net (code "190") (name "unconnected-(U3801B-DNU_8-PadAA12)") (class "Default")
      (node (ref "U3801") (pin "AA12") (pinfunction "DNU_8_AA12") (pintype "passive+no_connect"))
    )
    (net (code "191") (name "unconnected-(U3801B-DNU_9-PadAB1)") (class "Default")
      (node (ref "U3801") (pin "AB1") (pinfunction "DNU_9_AB1") (pintype "passive+no_connect"))
    )
    (net (code "192") (name "unconnected-(U3801B-DNU_10-PadAB2)") (class "Default")
      (node (ref "U3801") (pin "AB2") (pinfunction "DNU_10_AB2") (pintype "passive+no_connect"))
    )
    (net (code "193") (name "unconnected-(U3801B-DNU_11-PadAB11)") (class "Default")
      (node (ref "U3801") (pin "AB11") (pinfunction "DNU_11_AB11") (pintype "passive+no_connect"))
    )
    (net (code "194") (name "unconnected-(U3801B-DNU_12-PadAB12)") (class "Default")
      (node (ref "U3801") (pin "AB12") (pinfunction "DNU_12_AB12") (pintype "passive+no_connect"))
    )
  )
)
